# RT_SUPER__MK76__A.net
KiCad netlist of a schematic drawn in Altium Designer
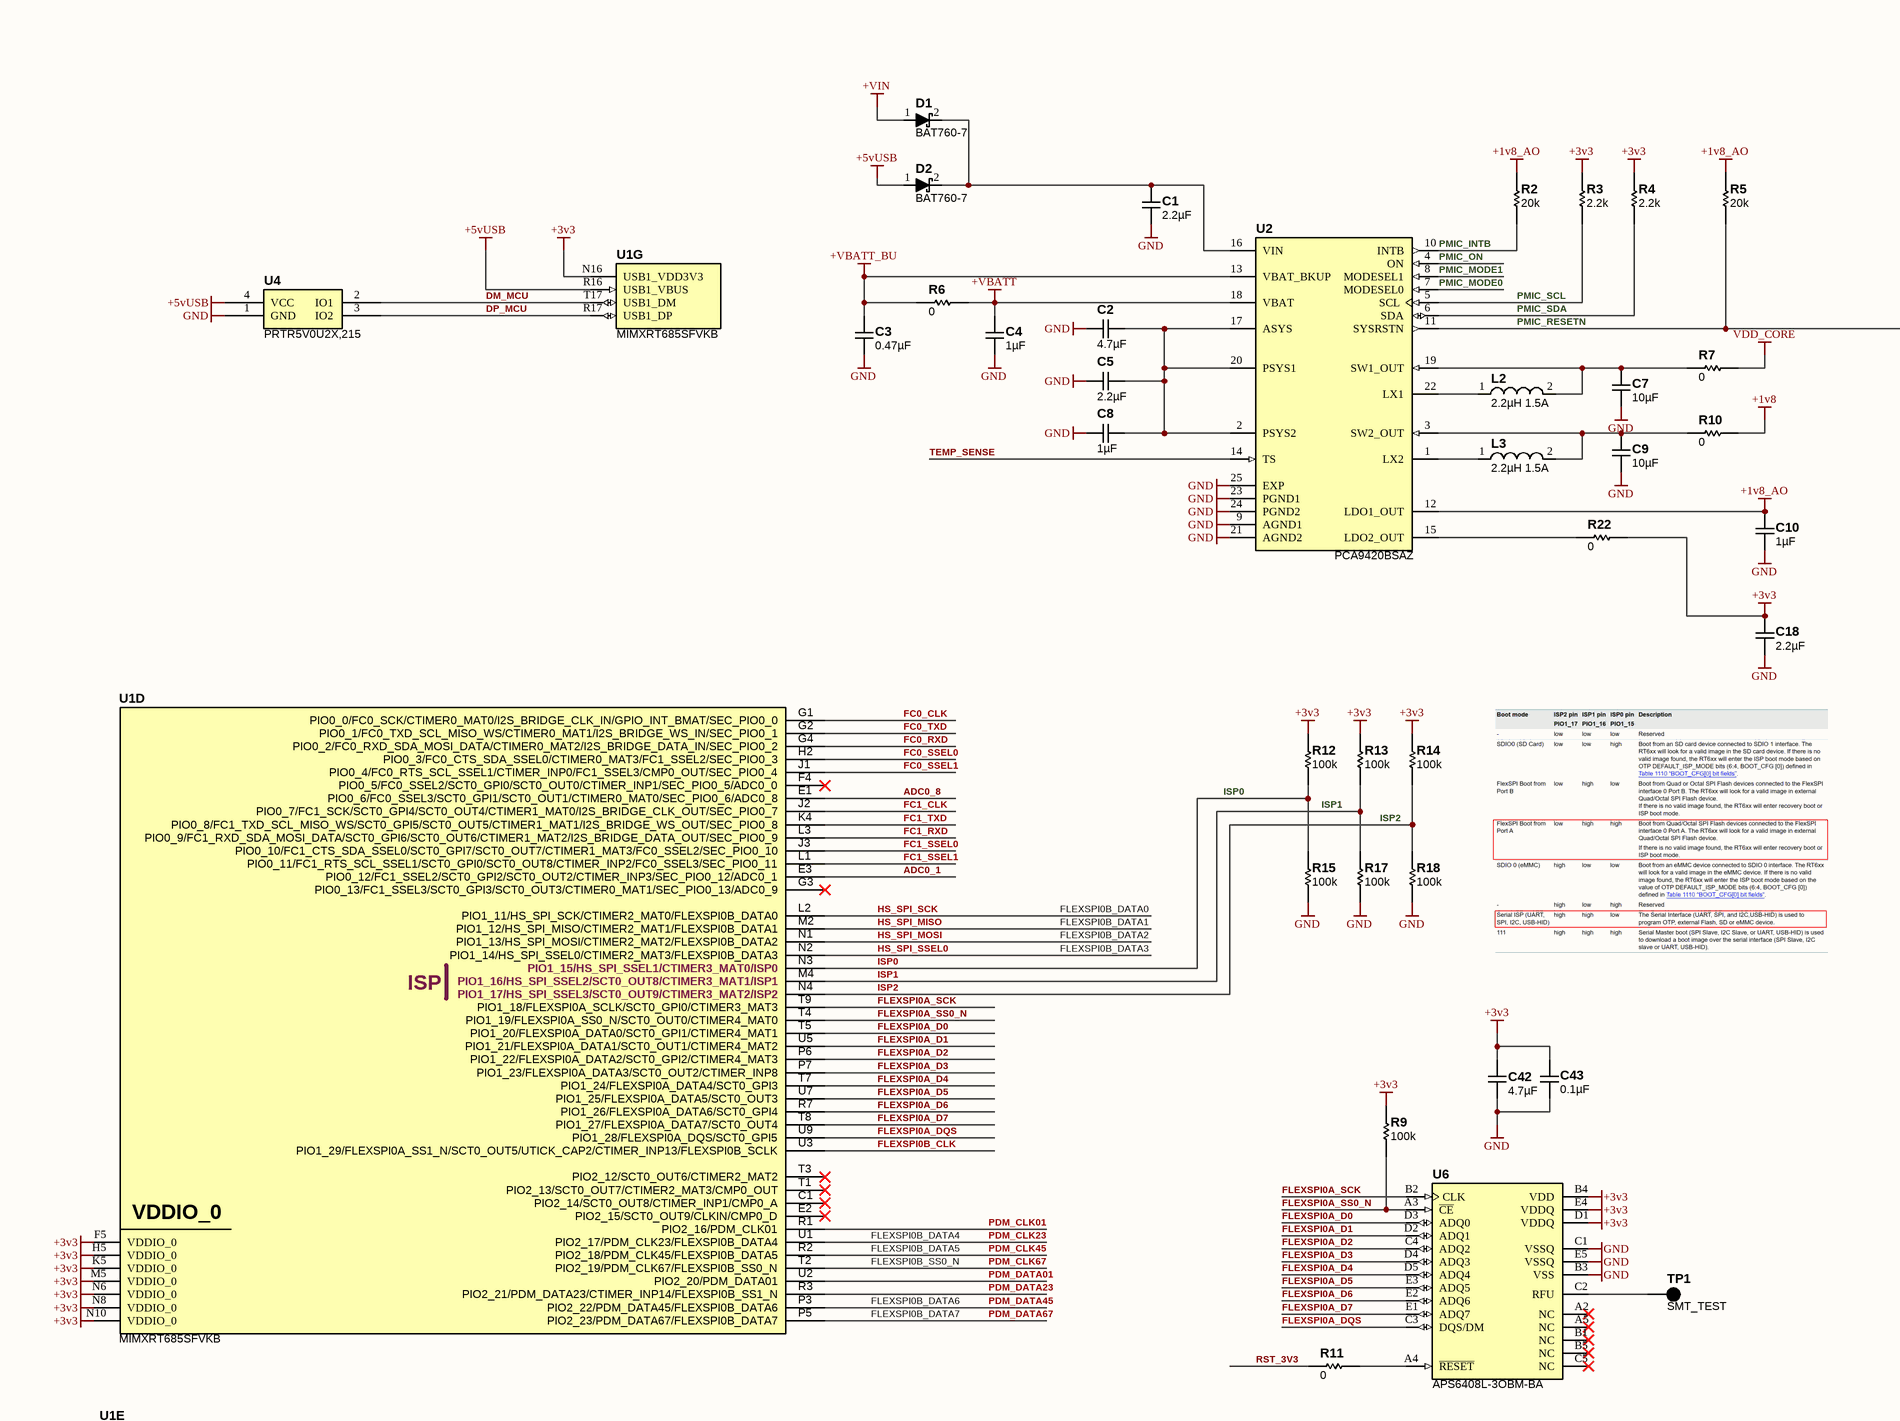
[diagram p0: RT_SUPER__MK76__A.SchDoc, top left]
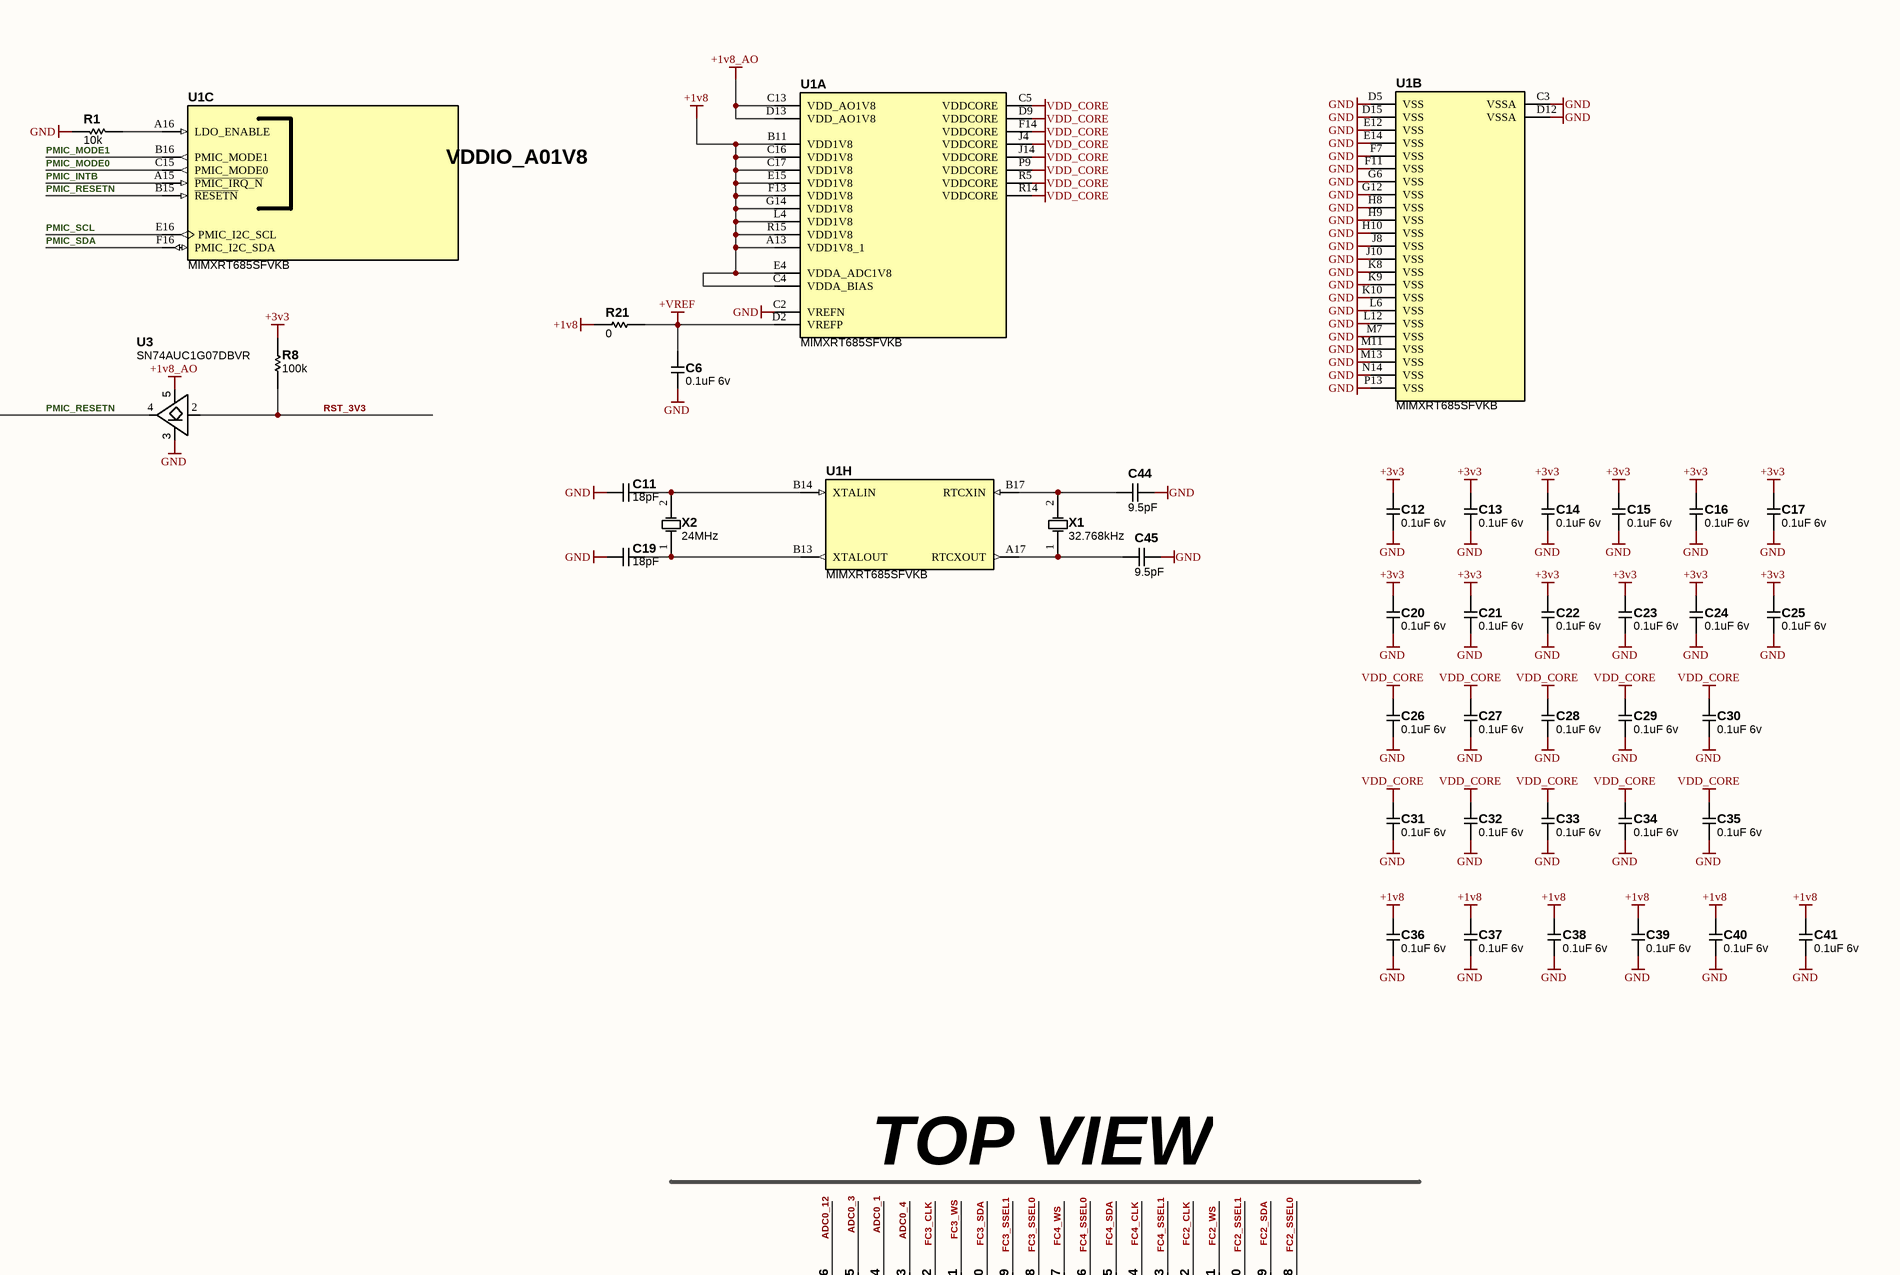
[diagram p1: RT_SUPER__MK76__A.SchDoc, top right]
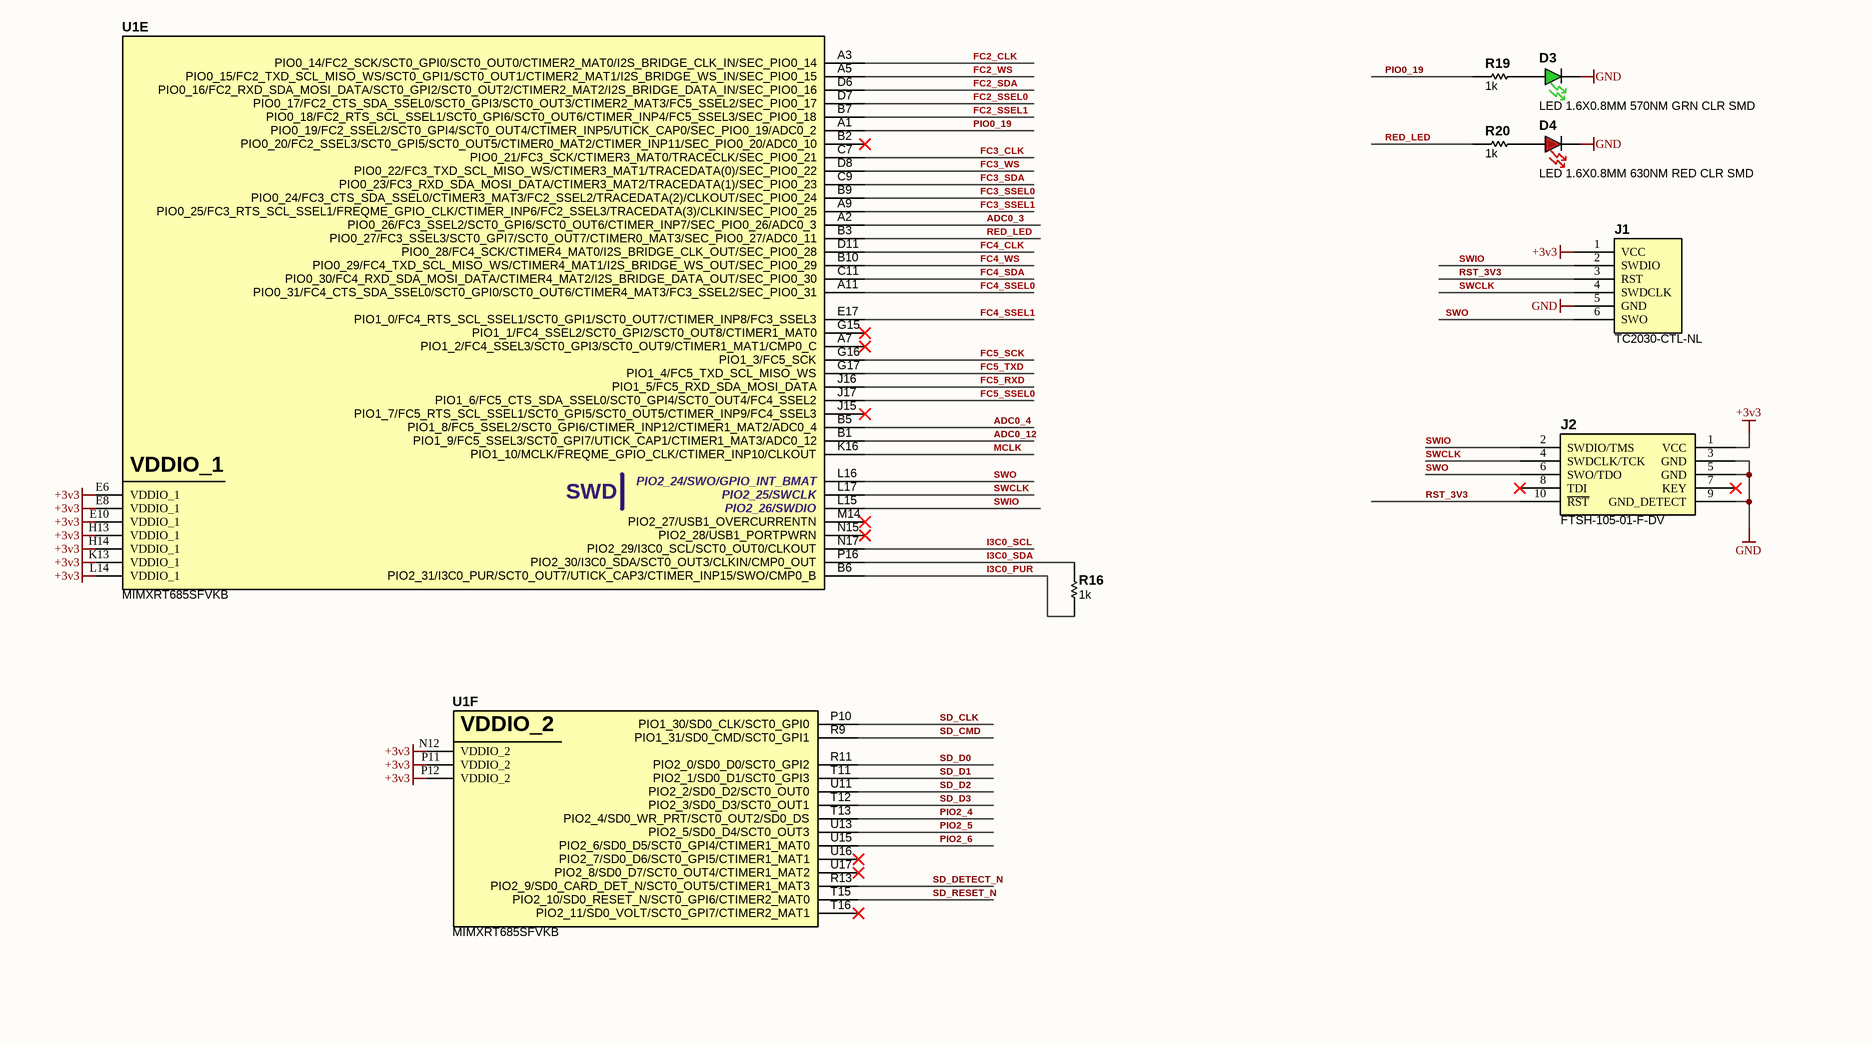
[diagram p2: RT_SUPER__MK76__A.SchDoc, bottom left]
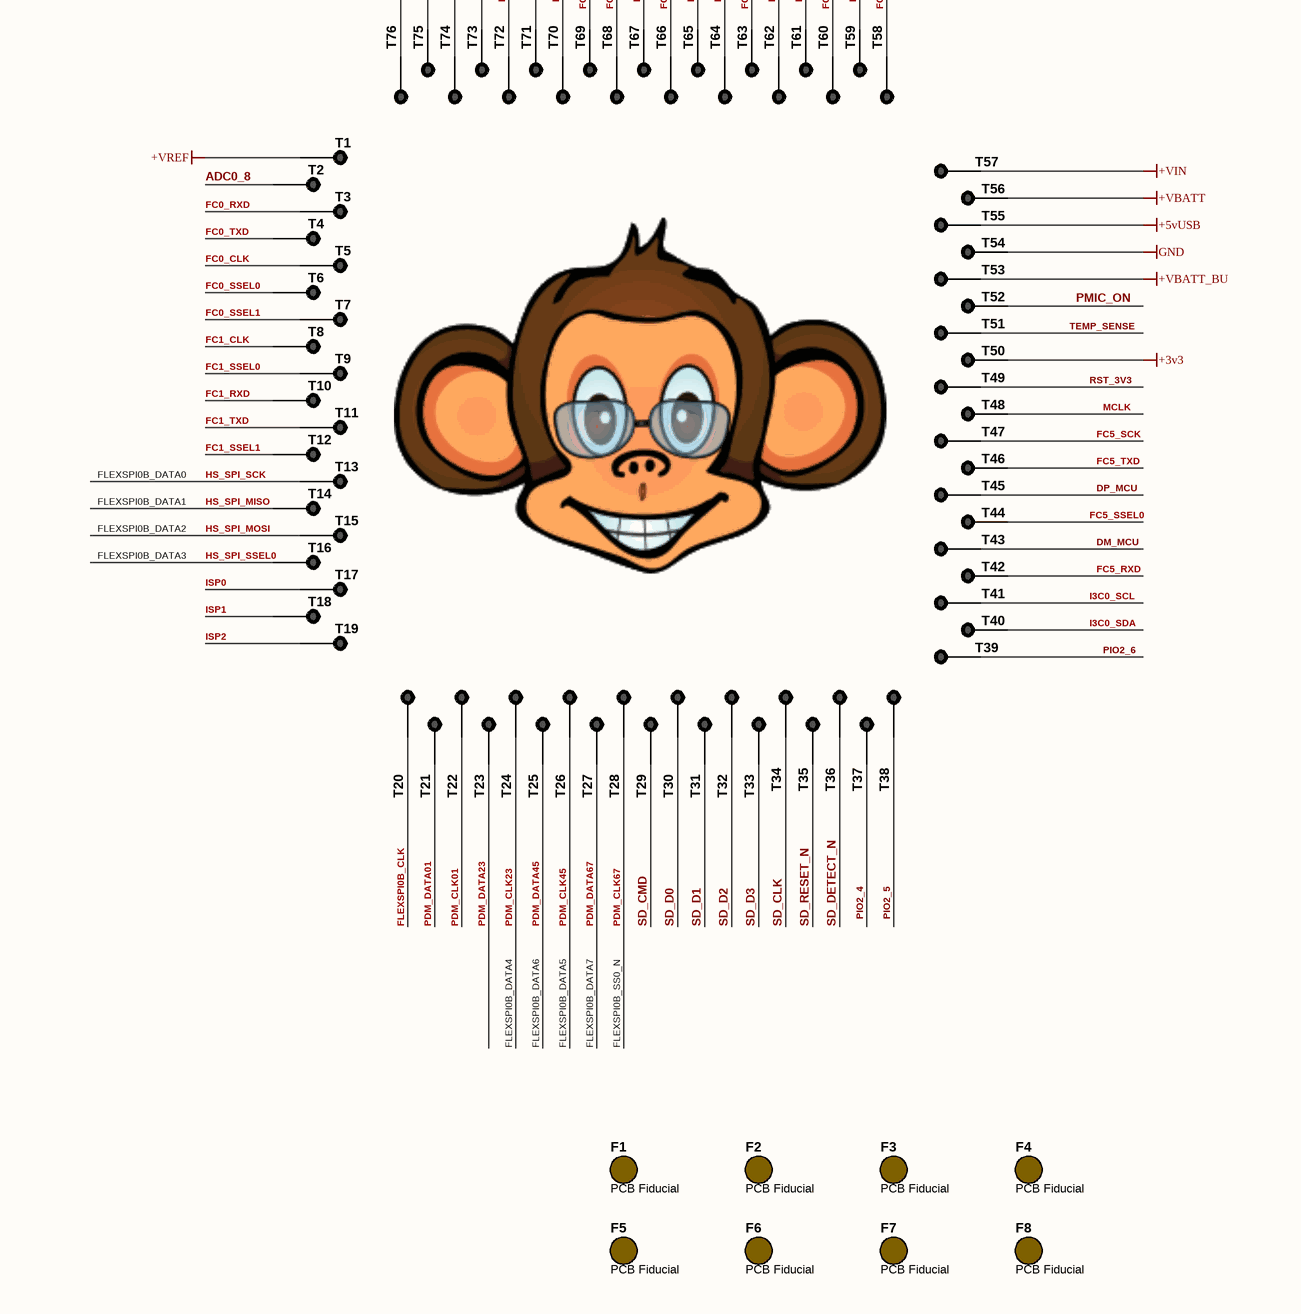
[diagram p3: RT_SUPER__MK76__A.SchDoc, bottom right]

(export (version "E")
  (design (tool "Eeschema 10.0.6"))
  (components
    (comp (ref "C1")
      (value "2.2µF")
      (footprint "C0603_0.90MM_MD")
      (description "CAP CER 2.2UF 6.3V X7R 0603")
      (fields
        (field (name "MANUFACTURER PART NUMBER") "GCM188R70J225KE22D")
        (field (name "MANUFACTURER") "Murata Electronics")
      )
      (libsource (lib "Capacitors - Murata - AEC-Q200") (part "C_2P_NP"))
    )
    (comp (ref "C2")
      (value "4.7µF")
      (footprint "C0603_1.00MM_MD")
      (description "CAP CER 4.7UF 6.3V X7S 0603")
      (fields
        (field (name "MANUFACTURER PART NUMBER") "GCJ188C70J475KE02D")
        (field (name "MANUFACTURER") "Murata Electronics")
      )
      (libsource (lib "Capacitors - Murata - AEC-Q200") (part "C_2P_NP"))
    )
    (comp (ref "C3")
      (value "0.47µF")
      (footprint "C0402_0.55MM_HD")
      (description "CAP CER 0.47UF 25V X5R 0402")
      (fields
        (field (name "MANUFACTURER PART NUMBER") "GRT155R61E474KE01D")
        (field (name "MANUFACTURER") "Murata Electronics")
      )
      (libsource (lib "Capacitors - Murata - AEC-Q200") (part "C_2P_NP"))
    )
    (comp (ref "C4")
      (value "1µF")
      (footprint "C0402_0.55MM_HD")
      (description "CAP CER 1UF 10V X7S 0402")
      (fields
        (field (name "MANUFACTURER PART NUMBER") "GCM155C71A105KE38D")
        (field (name "MANUFACTURER") "Murata Electronics")
      )
      (libsource (lib "Capacitors - Murata - AEC-Q200") (part "C_2P_NP"))
    )
    (comp (ref "C5")
      (value "2.2µF")
      (footprint "C0603_0.90MM_MD")
      (description "CAP CER 2.2UF 6.3V X7R 0603")
      (fields
        (field (name "MANUFACTURER PART NUMBER") "GCM188R70J225KE22D")
        (field (name "MANUFACTURER") "Murata Electronics")
      )
      (libsource (lib "Capacitors - Murata - AEC-Q200") (part "C_2P_NP"))
    )
    (comp (ref "C6")
      (value "0.1uF 6v")
      (footprint "C0201_PERFECT")
      (description "Cap Ceramic 0.1uF 6.3VDC X5R 10% SMD 0201 Paper T/R")
      (fields
        (field (name "MANUFACTURER PART NUMBER") "CC0201KRX5R5BB104")
        (field (name "MANUFACTURER") "Yageo")
      )
      (libsource (lib "eCapacitors") (part "CC0201KRX5R5BB104"))
    )
    (comp (ref "C7")
      (value "10µF")
      (footprint "C0603_0.90MM_MD")
      (description "CAP CER 10UF 10V X5R 0603")
      (fields
        (field (name "MANUFACTURER PART NUMBER") "GRT188R61A106ME13D")
        (field (name "MANUFACTURER") "Murata Electronics")
      )
      (libsource (lib "Capacitors - Murata - AEC-Q200") (part "C_2P_NP"))
    )
    (comp (ref "C8")
      (value "1µF")
      (footprint "C0402_0.55MM_HD")
      (description "CAP CER 1UF 10V X7S 0402")
      (fields
        (field (name "MANUFACTURER PART NUMBER") "GCM155C71A105KE38D")
        (field (name "MANUFACTURER") "Murata Electronics")
      )
      (libsource (lib "Capacitors - Murata - AEC-Q200") (part "C_2P_NP"))
    )
    (comp (ref "C9")
      (value "10µF")
      (footprint "C0603_0.90MM_MD")
      (description "CAP CER 10UF 10V X5R 0603")
      (fields
        (field (name "MANUFACTURER PART NUMBER") "GRT188R61A106ME13D")
        (field (name "MANUFACTURER") "Murata Electronics")
      )
      (libsource (lib "Capacitors - Murata - AEC-Q200") (part "C_2P_NP"))
    )
    (comp (ref "C10")
      (value "1µF")
      (footprint "C0402_0.55MM_HD")
      (description "CAP CER 1UF 10V X7S 0402")
      (fields
        (field (name "MANUFACTURER PART NUMBER") "GCM155C71A105KE38D")
        (field (name "MANUFACTURER") "Murata Electronics")
      )
      (libsource (lib "Capacitors - Murata - AEC-Q200") (part "C_2P_NP"))
    )
    (comp (ref "C11")
      (value "18pF")
      (footprint "C0402_0.55MM_HD")
      (description "CAP CER 18PF 50V C0G 0402")
      (fields
        (field (name "MANUFACTURER PART NUMBER") "CGA2B2C0G1H180J050BA")
        (field (name "MANUFACTURER") "TDK Corporation")
      )
      (libsource (lib "Capacitors - TDK- AEC-Q200") (part "C_2P_NP"))
    )
    (comp (ref "C12")
      (value "0.1uF 6v")
      (footprint "C0201_PERFECT")
      (description "Cap Ceramic 0.1uF 6.3VDC X5R 10% SMD 0201 Paper T/R")
      (fields
        (field (name "MANUFACTURER PART NUMBER") "CC0201KRX5R5BB104")
        (field (name "MANUFACTURER") "Yageo")
      )
      (libsource (lib "eCapacitors") (part "CC0201KRX5R5BB104"))
    )
    (comp (ref "C13")
      (value "0.1uF 6v")
      (footprint "C0201_PERFECT")
      (description "Cap Ceramic 0.1uF 6.3VDC X5R 10% SMD 0201 Paper T/R")
      (fields
        (field (name "MANUFACTURER PART NUMBER") "CC0201KRX5R5BB104")
        (field (name "MANUFACTURER") "Yageo")
      )
      (libsource (lib "eCapacitors") (part "CC0201KRX5R5BB104"))
    )
    (comp (ref "C14")
      (value "0.1uF 6v")
      (footprint "C0201_PERFECT")
      (description "Cap Ceramic 0.1uF 6.3VDC X5R 10% SMD 0201 Paper T/R")
      (fields
        (field (name "MANUFACTURER PART NUMBER") "CC0201KRX5R5BB104")
        (field (name "MANUFACTURER") "Yageo")
      )
      (libsource (lib "eCapacitors") (part "CC0201KRX5R5BB104"))
    )
    (comp (ref "C15")
      (value "0.1uF 6v")
      (footprint "C0201_PERFECT")
      (description "Cap Ceramic 0.1uF 6.3VDC X5R 10% SMD 0201 Paper T/R")
      (fields
        (field (name "MANUFACTURER PART NUMBER") "CC0201KRX5R5BB104")
        (field (name "MANUFACTURER") "Yageo")
      )
      (libsource (lib "eCapacitors") (part "CC0201KRX5R5BB104"))
    )
    (comp (ref "C16")
      (value "0.1uF 6v")
      (footprint "C0201_PERFECT")
      (description "Cap Ceramic 0.1uF 6.3VDC X5R 10% SMD 0201 Paper T/R")
      (fields
        (field (name "MANUFACTURER PART NUMBER") "CC0201KRX5R5BB104")
        (field (name "MANUFACTURER") "Yageo")
      )
      (libsource (lib "eCapacitors") (part "CC0201KRX5R5BB104"))
    )
    (comp (ref "C17")
      (value "0.1uF 6v")
      (footprint "C0201_PERFECT")
      (description "Cap Ceramic 0.1uF 6.3VDC X5R 10% SMD 0201 Paper T/R")
      (fields
        (field (name "MANUFACTURER PART NUMBER") "CC0201KRX5R5BB104")
        (field (name "MANUFACTURER") "Yageo")
      )
      (libsource (lib "eCapacitors") (part "CC0201KRX5R5BB104"))
    )
    (comp (ref "C18")
      (value "2.2µF")
      (footprint "C0603_0.90MM_MD")
      (description "CAP CER 2.2UF 6.3V X7R 0603")
      (fields
        (field (name "MANUFACTURER PART NUMBER") "GCM188R70J225KE22D")
        (field (name "MANUFACTURER") "Murata Electronics")
      )
      (libsource (lib "Capacitors - Murata - AEC-Q200") (part "C_2P_NP"))
    )
    (comp (ref "C19")
      (value "18pF")
      (footprint "C0402_0.55MM_HD")
      (description "CAP CER 18PF 50V C0G 0402")
      (fields
        (field (name "MANUFACTURER PART NUMBER") "CGA2B2C0G1H180J050BA")
        (field (name "MANUFACTURER") "TDK Corporation")
      )
      (libsource (lib "Capacitors - TDK- AEC-Q200") (part "C_2P_NP"))
    )
    (comp (ref "C20")
      (value "0.1uF 6v")
      (footprint "C0201_PERFECT")
      (description "Cap Ceramic 0.1uF 6.3VDC X5R 10% SMD 0201 Paper T/R")
      (fields
        (field (name "MANUFACTURER PART NUMBER") "CC0201KRX5R5BB104")
        (field (name "MANUFACTURER") "Yageo")
      )
      (libsource (lib "eCapacitors") (part "CC0201KRX5R5BB104"))
    )
    (comp (ref "C21")
      (value "0.1uF 6v")
      (footprint "C0201_PERFECT")
      (description "Cap Ceramic 0.1uF 6.3VDC X5R 10% SMD 0201 Paper T/R")
      (fields
        (field (name "MANUFACTURER PART NUMBER") "CC0201KRX5R5BB104")
        (field (name "MANUFACTURER") "Yageo")
      )
      (libsource (lib "eCapacitors") (part "CC0201KRX5R5BB104"))
    )
    (comp (ref "C22")
      (value "0.1uF 6v")
      (footprint "C0201_PERFECT")
      (description "Cap Ceramic 0.1uF 6.3VDC X5R 10% SMD 0201 Paper T/R")
      (fields
        (field (name "MANUFACTURER PART NUMBER") "CC0201KRX5R5BB104")
        (field (name "MANUFACTURER") "Yageo")
      )
      (libsource (lib "eCapacitors") (part "CC0201KRX5R5BB104"))
    )
    (comp (ref "C23")
      (value "0.1uF 6v")
      (footprint "C0201_PERFECT")
      (description "Cap Ceramic 0.1uF 6.3VDC X5R 10% SMD 0201 Paper T/R")
      (fields
        (field (name "MANUFACTURER PART NUMBER") "CC0201KRX5R5BB104")
        (field (name "MANUFACTURER") "Yageo")
      )
      (libsource (lib "eCapacitors") (part "CC0201KRX5R5BB104"))
    )
    (comp (ref "C24")
      (value "0.1uF 6v")
      (footprint "C0201_PERFECT")
      (description "Cap Ceramic 0.1uF 6.3VDC X5R 10% SMD 0201 Paper T/R")
      (fields
        (field (name "MANUFACTURER PART NUMBER") "CC0201KRX5R5BB104")
        (field (name "MANUFACTURER") "Yageo")
      )
      (libsource (lib "eCapacitors") (part "CC0201KRX5R5BB104"))
    )
    (comp (ref "C25")
      (value "0.1uF 6v")
      (footprint "C0201_PERFECT")
      (description "Cap Ceramic 0.1uF 6.3VDC X5R 10% SMD 0201 Paper T/R")
      (fields
        (field (name "MANUFACTURER PART NUMBER") "CC0201KRX5R5BB104")
        (field (name "MANUFACTURER") "Yageo")
      )
      (libsource (lib "eCapacitors") (part "CC0201KRX5R5BB104"))
    )
    (comp (ref "C26")
      (value "0.1uF 6v")
      (footprint "C0201_PERFECT")
      (description "Cap Ceramic 0.1uF 6.3VDC X5R 10% SMD 0201 Paper T/R")
      (fields
        (field (name "MANUFACTURER PART NUMBER") "CC0201KRX5R5BB104")
        (field (name "MANUFACTURER") "Yageo")
      )
      (libsource (lib "eCapacitors") (part "CC0201KRX5R5BB104"))
    )
    (comp (ref "C27")
      (value "0.1uF 6v")
      (footprint "C0201_PERFECT")
      (description "Cap Ceramic 0.1uF 6.3VDC X5R 10% SMD 0201 Paper T/R")
      (fields
        (field (name "MANUFACTURER PART NUMBER") "CC0201KRX5R5BB104")
        (field (name "MANUFACTURER") "Yageo")
      )
      (libsource (lib "eCapacitors") (part "CC0201KRX5R5BB104"))
    )
    (comp (ref "C28")
      (value "0.1uF 6v")
      (footprint "C0201_PERFECT")
      (description "Cap Ceramic 0.1uF 6.3VDC X5R 10% SMD 0201 Paper T/R")
      (fields
        (field (name "MANUFACTURER PART NUMBER") "CC0201KRX5R5BB104")
        (field (name "MANUFACTURER") "Yageo")
      )
      (libsource (lib "eCapacitors") (part "CC0201KRX5R5BB104"))
    )
    (comp (ref "C29")
      (value "0.1uF 6v")
      (footprint "C0201_PERFECT")
      (description "Cap Ceramic 0.1uF 6.3VDC X5R 10% SMD 0201 Paper T/R")
      (fields
        (field (name "MANUFACTURER PART NUMBER") "CC0201KRX5R5BB104")
        (field (name "MANUFACTURER") "Yageo")
      )
      (libsource (lib "eCapacitors") (part "CC0201KRX5R5BB104"))
    )
    (comp (ref "C30")
      (value "0.1uF 6v")
      (footprint "C0201_PERFECT")
      (description "Cap Ceramic 0.1uF 6.3VDC X5R 10% SMD 0201 Paper T/R")
      (fields
        (field (name "MANUFACTURER PART NUMBER") "CC0201KRX5R5BB104")
        (field (name "MANUFACTURER") "Yageo")
      )
      (libsource (lib "eCapacitors") (part "CC0201KRX5R5BB104"))
    )
    (comp (ref "C31")
      (value "0.1uF 6v")
      (footprint "C0201_PERFECT")
      (description "Cap Ceramic 0.1uF 6.3VDC X5R 10% SMD 0201 Paper T/R")
      (fields
        (field (name "MANUFACTURER PART NUMBER") "CC0201KRX5R5BB104")
        (field (name "MANUFACTURER") "Yageo")
      )
      (libsource (lib "eCapacitors") (part "CC0201KRX5R5BB104"))
    )
    (comp (ref "C32")
      (value "0.1uF 6v")
      (footprint "C0201_PERFECT")
      (description "Cap Ceramic 0.1uF 6.3VDC X5R 10% SMD 0201 Paper T/R")
      (fields
        (field (name "MANUFACTURER PART NUMBER") "CC0201KRX5R5BB104")
        (field (name "MANUFACTURER") "Yageo")
      )
      (libsource (lib "eCapacitors") (part "CC0201KRX5R5BB104"))
    )
    (comp (ref "C33")
      (value "0.1uF 6v")
      (footprint "C0201_PERFECT")
      (description "Cap Ceramic 0.1uF 6.3VDC X5R 10% SMD 0201 Paper T/R")
      (fields
        (field (name "MANUFACTURER PART NUMBER") "CC0201KRX5R5BB104")
        (field (name "MANUFACTURER") "Yageo")
      )
      (libsource (lib "eCapacitors") (part "CC0201KRX5R5BB104"))
    )
    (comp (ref "C34")
      (value "0.1uF 6v")
      (footprint "C0201_PERFECT")
      (description "Cap Ceramic 0.1uF 6.3VDC X5R 10% SMD 0201 Paper T/R")
      (fields
        (field (name "MANUFACTURER PART NUMBER") "CC0201KRX5R5BB104")
        (field (name "MANUFACTURER") "Yageo")
      )
      (libsource (lib "eCapacitors") (part "CC0201KRX5R5BB104"))
    )
    (comp (ref "C35")
      (value "0.1uF 6v")
      (footprint "C0201_PERFECT")
      (description "Cap Ceramic 0.1uF 6.3VDC X5R 10% SMD 0201 Paper T/R")
      (fields
        (field (name "MANUFACTURER PART NUMBER") "CC0201KRX5R5BB104")
        (field (name "MANUFACTURER") "Yageo")
      )
      (libsource (lib "eCapacitors") (part "CC0201KRX5R5BB104"))
    )
    (comp (ref "C36")
      (value "0.1uF 6v")
      (footprint "C0201_PERFECT")
      (description "Cap Ceramic 0.1uF 6.3VDC X5R 10% SMD 0201 Paper T/R")
      (fields
        (field (name "MANUFACTURER PART NUMBER") "CC0201KRX5R5BB104")
        (field (name "MANUFACTURER") "Yageo")
      )
      (libsource (lib "eCapacitors") (part "CC0201KRX5R5BB104"))
    )
    (comp (ref "C37")
      (value "0.1uF 6v")
      (footprint "C0201_PERFECT")
      (description "Cap Ceramic 0.1uF 6.3VDC X5R 10% SMD 0201 Paper T/R")
      (fields
        (field (name "MANUFACTURER PART NUMBER") "CC0201KRX5R5BB104")
        (field (name "MANUFACTURER") "Yageo")
      )
      (libsource (lib "eCapacitors") (part "CC0201KRX5R5BB104"))
    )
    (comp (ref "C38")
      (value "0.1uF 6v")
      (footprint "C0201_PERFECT")
      (description "Cap Ceramic 0.1uF 6.3VDC X5R 10% SMD 0201 Paper T/R")
      (fields
        (field (name "MANUFACTURER PART NUMBER") "CC0201KRX5R5BB104")
        (field (name "MANUFACTURER") "Yageo")
      )
      (libsource (lib "eCapacitors") (part "CC0201KRX5R5BB104"))
    )
    (comp (ref "C39")
      (value "0.1uF 6v")
      (footprint "C0201_PERFECT")
      (description "Cap Ceramic 0.1uF 6.3VDC X5R 10% SMD 0201 Paper T/R")
      (fields
        (field (name "MANUFACTURER PART NUMBER") "CC0201KRX5R5BB104")
        (field (name "MANUFACTURER") "Yageo")
      )
      (libsource (lib "eCapacitors") (part "CC0201KRX5R5BB104"))
    )
    (comp (ref "C40")
      (value "0.1uF 6v")
      (footprint "C0201_PERFECT")
      (description "Cap Ceramic 0.1uF 6.3VDC X5R 10% SMD 0201 Paper T/R")
      (fields
        (field (name "MANUFACTURER PART NUMBER") "CC0201KRX5R5BB104")
        (field (name "MANUFACTURER") "Yageo")
      )
      (libsource (lib "eCapacitors") (part "CC0201KRX5R5BB104"))
    )
    (comp (ref "C41")
      (value "0.1uF 6v")
      (footprint "C0201_PERFECT")
      (description "Cap Ceramic 0.1uF 6.3VDC X5R 10% SMD 0201 Paper T/R")
      (fields
        (field (name "MANUFACTURER PART NUMBER") "CC0201KRX5R5BB104")
        (field (name "MANUFACTURER") "Yageo")
      )
      (libsource (lib "eCapacitors") (part "CC0201KRX5R5BB104"))
    )
    (comp (ref "C42")
      (value "4.7µF")
      (footprint "C0603_1.00MM_MD")
      (description "CAP CER 4.7UF 6.3V X7S 0603")
      (fields
        (field (name "MANUFACTURER PART NUMBER") "GCJ188C70J475KE02D")
        (field (name "MANUFACTURER") "Murata Electronics")
      )
      (libsource (lib "Capacitors - Murata - AEC-Q200") (part "C_2P_NP"))
    )
    (comp (ref "C43")
      (value "0.1µF")
      (footprint "C0402_0.55MM_MD")
      (description "CAP CER 0.1UF 16V X7R 0402")
      (fields
        (field (name "MANUFACTURER PART NUMBER") "CGA2B1X7R1C104K050BC")
        (field (name "MANUFACTURER") "TDK Corporation")
      )
      (libsource (lib "Capacitors - TDK- AEC-Q200") (part "C_2P_NP"))
    )
    (comp (ref "C44")
      (value "9.5pF")
      (footprint "PERFECT_0402")
      (description "CAP CER 9.5PF 50V C0G/NP0 0402")
      (fields
        (field (name "MANUFACTURER PART NUMBER") "GCQ1555C1H9R5BB01D")
        (field (name "MANUFACTURER") "Murata Electronics")
      )
      (libsource (lib "Capacitors - Murata - AEC-Q200") (part "C_2P_NP"))
    )
    (comp (ref "C45")
      (value "9.5pF")
      (footprint "PERFECT_0402")
      (description "CAP CER 9.5PF 50V C0G/NP0 0402")
      (fields
        (field (name "MANUFACTURER PART NUMBER") "GCQ1555C1H9R5BB01D")
        (field (name "MANUFACTURER") "Murata Electronics")
      )
      (libsource (lib "Capacitors - Murata - AEC-Q200") (part "C_2P_NP"))
    )
    (comp (ref "D1")
      (value "BAT760-7")
      (footprint "D_SOD-323_P")
      (description "DIODE SCHOTTKY 30V 1A SOD323")
      (fields (field (name "MANUFACTURER") "Diodes Inc"))
      (libsource (lib "Diodes") (part "DS_1A_2C"))
    )
    (comp (ref "D2")
      (value "BAT760-7")
      (footprint "D_SOD-323_P")
      (description "DIODE SCHOTTKY 30V 1A SOD323")
      (fields (field (name "MANUFACTURER") "Diodes Inc"))
      (libsource (lib "Diodes") (part "DS_1A_2C"))
    )
    (comp (ref "D3")
      (value "LED 1.6X0.8MM 570NM GRN CLR SMD")
      (footprint "LED_0603 - GREEN")
      (fields
        (field (name "MANUFACTURER") "Kingbright Corp")
        (field (name "MANUFACTURER PART NUMBER") "APT1608CGCK")
      )
      (libsource (lib "eDiode") (part "APT1608CGCK"))
    )
    (comp (ref "D4")
      (value "LED 1.6X0.8MM 630NM RED CLR SMD")
      (footprint "LED_0603 - RED")
      (fields
        (field (name "MANUFACTURER") "Kingbright Corp")
        (field (name "MANUFACTURER PART NUMBER") "APT1608SURCK")
      )
      (libsource (lib "eDiode") (part "APT1608SURCK"))
    )
    (comp (ref "F1")
      (value "PCB Fiducial")
      (footprint "Fiducial 1mm - 2mm")
      (libsource (lib "eFiducial") (part "Fiducial"))
    )
    (comp (ref "F2")
      (value "PCB Fiducial")
      (footprint "Fiducial 1mm - 2mm")
      (libsource (lib "eFiducial") (part "Fiducial"))
    )
    (comp (ref "F3")
      (value "PCB Fiducial")
      (footprint "Fiducial 1mm - 2mm")
      (libsource (lib "eFiducial") (part "Fiducial"))
    )
    (comp (ref "F4")
      (value "PCB Fiducial")
      (footprint "Fiducial 1mm - 2mm")
      (libsource (lib "eFiducial") (part "Fiducial"))
    )
    (comp (ref "F5")
      (value "PCB Fiducial")
      (footprint "Fiducial 1mm - 2mm")
      (libsource (lib "eFiducial") (part "Fiducial"))
    )
    (comp (ref "F6")
      (value "PCB Fiducial")
      (footprint "Fiducial 1mm - 2mm")
      (libsource (lib "eFiducial") (part "Fiducial"))
    )
    (comp (ref "F7")
      (value "PCB Fiducial")
      (footprint "Fiducial 1mm - 2mm")
      (libsource (lib "eFiducial") (part "Fiducial"))
    )
    (comp (ref "F8")
      (value "PCB Fiducial")
      (footprint "Fiducial 1mm - 2mm")
      (libsource (lib "eFiducial") (part "Fiducial"))
    )
    (comp (ref "J1")
      (value "TC2030‐CTL‐NL")
      (footprint "TC2030 NO LATCH")
      (description "Tag Connect Pads - No latching Clips - ARM")
      (libsource (lib "eConnector_Debug") (part "TC2030‐CTL‐NL"))
    )
    (comp (ref "J2")
      (value "FTSH-105-01-F-DV")
      (footprint "FTSH-105-01-F-DV-K-A")
      (description "SAMTEC - FTSH-105-01-F-DV - .050 X .050")
      (fields (field (name "MANUFACTURER") "SAMTEC"))
      (libsource (lib "eConnector") (part "CORTEX-DEBUG"))
    )
    (comp (ref "L2")
      (value "2.2µH 1.5A")
      (footprint "L_NRH3012")
      (description "Inductor 2.2µH 1.5A")
      (fields
        (field (name "MANUFACTURER PART NUMBER") "NRH3012T2R2MN")
        (field (name "MANUFACTURER") "Taiyo Yuden")
      )
      (libsource (lib "Inductors") (part "L_2P"))
    )
    (comp (ref "L3")
      (value "2.2µH 1.5A")
      (footprint "L_NRH3012")
      (description "Inductor 2.2µH 1.5A")
      (fields
        (field (name "MANUFACTURER PART NUMBER") "NRH3012T2R2MN")
        (field (name "MANUFACTURER") "Taiyo Yuden")
      )
      (libsource (lib "Inductors") (part "L_2P"))
    )
    (comp (ref "R1")
      (value "10k")
      (footprint "R0402_0.40MM_HD")
      (description "RES 10K OHM 1/10W 1% 0402 SMD")
      (fields
        (field (name "MANUFACTURER PART NUMBER") "ERJ-2RKF1002X")
        (field (name "MANUFACTURER") "Panasonic Electronic Components")
      )
      (libsource (lib "Resistors - Panasonic - AEC-Q200") (part "R_2P"))
    )
    (comp (ref "R2")
      (value "20k")
      (footprint "R0402_0.40MM_HD")
      (description "RES 20K OHM 1/10W 1% 0402 SMD")
      (fields
        (field (name "MANUFACTURER PART NUMBER") "ERJ-2RKF2002X")
        (field (name "MANUFACTURER") "Panasonic Electronic Components")
      )
      (libsource (lib "Resistors - Panasonic - AEC-Q200") (part "R_2P"))
    )
    (comp (ref "R3")
      (value "2.2k")
      (footprint "R0402_0.40MM_HD")
      (description "RES 2.2K OHM 1/10W 1% 0402 SMD")
      (fields
        (field (name "MANUFACTURER PART NUMBER") "ERJ-2RKF2201X")
        (field (name "MANUFACTURER") "Panasonic Electronic Components")
      )
      (libsource (lib "Resistors - Panasonic - AEC-Q200") (part "R_2P"))
    )
    (comp (ref "R4")
      (value "2.2k")
      (footprint "R0402_0.40MM_HD")
      (description "RES 2.2K OHM 1/10W 1% 0402 SMD")
      (fields
        (field (name "MANUFACTURER PART NUMBER") "ERJ-2RKF2201X")
        (field (name "MANUFACTURER") "Panasonic Electronic Components")
      )
      (libsource (lib "Resistors - Panasonic - AEC-Q200") (part "R_2P"))
    )
    (comp (ref "R5")
      (value "20k")
      (footprint "R0402_0.40MM_HD")
      (description "RES 20K OHM 1/10W 1% 0402 SMD")
      (fields
        (field (name "MANUFACTURER PART NUMBER") "ERJ-2RKF2002X")
        (field (name "MANUFACTURER") "Panasonic Electronic Components")
      )
      (libsource (lib "Resistors - Panasonic - AEC-Q200") (part "R_2P"))
    )
    (comp (ref "R6")
      (value "0")
      (footprint "R0402_0.40MM_HD")
      (description "RES 0.0 OHM 1/10W JUMP 0402 SMD")
      (fields
        (field (name "MANUFACTURER PART NUMBER") "ERJ-2GE0R00X")
        (field (name "MANUFACTURER") "Panasonic Electronic Components")
      )
      (libsource (lib "Resistors - Panasonic - AEC-Q200") (part "R_2P"))
    )
    (comp (ref "R7")
      (value "0")
      (footprint "R0402_0.40MM_HD")
      (description "RES 0.0 OHM 1/10W JUMP 0402 SMD")
      (fields
        (field (name "MANUFACTURER PART NUMBER") "ERJ-2GE0R00X")
        (field (name "MANUFACTURER") "Panasonic Electronic Components")
      )
      (libsource (lib "Resistors - Panasonic - AEC-Q200") (part "R_2P"))
    )
    (comp (ref "R8")
      (value "100k")
      (footprint "R0402_0.40MM_HD")
      (description "RES 100K OHM 1/10W 1% 0402 SMD")
      (fields
        (field (name "MANUFACTURER PART NUMBER") "ERJ-2RKF1003X")
        (field (name "MANUFACTURER") "Panasonic Electronic Components")
      )
      (libsource (lib "Resistors - Panasonic - AEC-Q200") (part "R_2P"))
    )
    (comp (ref "R9")
      (value "100k")
      (footprint "R0402_0.40MM_HD")
      (description "RES 100K OHM 1/10W 1% 0402 SMD")
      (fields
        (field (name "MANUFACTURER PART NUMBER") "ERJ-2RKF1003X")
        (field (name "MANUFACTURER") "Panasonic Electronic Components")
      )
      (libsource (lib "Resistors - Panasonic - AEC-Q200") (part "R_2P"))
    )
    (comp (ref "R10")
      (value "0")
      (footprint "R0402_0.40MM_HD")
      (description "RES 0.0 OHM 1/10W JUMP 0402 SMD")
      (fields
        (field (name "MANUFACTURER PART NUMBER") "ERJ-2GE0R00X")
        (field (name "MANUFACTURER") "Panasonic Electronic Components")
      )
      (libsource (lib "Resistors - Panasonic - AEC-Q200") (part "R_2P"))
    )
    (comp (ref "R11")
      (value "0")
      (footprint "R0402_0.40MM_HD")
      (description "RES 0.0 OHM 1/10W JUMP 0402 SMD")
      (fields
        (field (name "MANUFACTURER PART NUMBER") "ERJ-2GE0R00X")
        (field (name "MANUFACTURER") "Panasonic Electronic Components")
      )
      (libsource (lib "Resistors - Panasonic - AEC-Q200") (part "R_2P"))
    )
    (comp (ref "R12")
      (value "100k")
      (footprint "R0402_0.40MM_HD")
      (description "RES 100K OHM 1/10W 1% 0402 SMD")
      (fields
        (field (name "MANUFACTURER PART NUMBER") "ERJ-2RKF1003X")
        (field (name "MANUFACTURER") "Panasonic Electronic Components")
      )
      (libsource (lib "Resistors - Panasonic - AEC-Q200") (part "R_2P"))
    )
    (comp (ref "R13")
      (value "100k")
      (footprint "R0402_0.40MM_HD")
      (description "RES 100K OHM 1/10W 1% 0402 SMD")
      (fields
        (field (name "MANUFACTURER PART NUMBER") "ERJ-2RKF1003X")
        (field (name "MANUFACTURER") "Panasonic Electronic Components")
      )
      (libsource (lib "Resistors - Panasonic - AEC-Q200") (part "R_2P"))
    )
    (comp (ref "R14")
      (value "100k")
      (footprint "R0402_0.40MM_HD")
      (description "RES 100K OHM 1/10W 1% 0402 SMD")
      (fields
        (field (name "MANUFACTURER PART NUMBER") "ERJ-2RKF1003X")
        (field (name "MANUFACTURER") "Panasonic Electronic Components")
      )
      (libsource (lib "Resistors - Panasonic - AEC-Q200") (part "R_2P"))
    )
    (comp (ref "R15")
      (value "100k")
      (footprint "R0402_0.40MM_HD")
      (description "RES 100K OHM 1/10W 1% 0402 SMD")
      (fields
        (field (name "MANUFACTURER PART NUMBER") "ERJ-2RKF1003X")
        (field (name "MANUFACTURER") "Panasonic Electronic Components")
      )
      (libsource (lib "Resistors - Panasonic - AEC-Q200") (part "R_2P"))
    )
    (comp (ref "R16")
      (value "1k")
      (footprint "R0402_0.40MM_HD")
      (description "RES 1K OHM 1/10W 1% 0402 SMD")
      (fields
        (field (name "MANUFACTURER PART NUMBER") "ERJ-2RKF1001X")
        (field (name "MANUFACTURER") "Panasonic Electronic Components")
      )
      (libsource (lib "Resistors - Panasonic - AEC-Q200") (part "R_2P"))
    )
    (comp (ref "R17")
      (value "100k")
      (footprint "R0402_0.40MM_HD")
      (description "RES 100K OHM 1/10W 1% 0402 SMD")
      (fields
        (field (name "MANUFACTURER PART NUMBER") "ERJ-2RKF1003X")
        (field (name "MANUFACTURER") "Panasonic Electronic Components")
      )
      (libsource (lib "Resistors - Panasonic - AEC-Q200") (part "R_2P"))
    )
    (comp (ref "R18")
      (value "100k")
      (footprint "R0402_0.40MM_HD")
      (description "RES 100K OHM 1/10W 1% 0402 SMD")
      (fields
        (field (name "MANUFACTURER PART NUMBER") "ERJ-2RKF1003X")
        (field (name "MANUFACTURER") "Panasonic Electronic Components")
      )
      (libsource (lib "Resistors - Panasonic - AEC-Q200") (part "R_2P"))
    )
    (comp (ref "R19")
      (value "1k")
      (footprint "R0402_0.40MM_HD")
      (description "RES 1K OHM 1/10W 1% 0402 SMD")
      (fields
        (field (name "MANUFACTURER PART NUMBER") "ERJ-2RKF1001X")
        (field (name "MANUFACTURER") "Panasonic Electronic Components")
      )
      (libsource (lib "Resistors - Panasonic - AEC-Q200") (part "R_2P"))
    )
    (comp (ref "R20")
      (value "1k")
      (footprint "R0402_0.40MM_HD")
      (description "RES 1K OHM 1/10W 1% 0402 SMD")
      (fields
        (field (name "MANUFACTURER PART NUMBER") "ERJ-2RKF1001X")
        (field (name "MANUFACTURER") "Panasonic Electronic Components")
      )
      (libsource (lib "Resistors - Panasonic - AEC-Q200") (part "R_2P"))
    )
    (comp (ref "R21")
      (value "0")
      (footprint "R0402_0.40MM_HD")
      (description "RES 0.0 OHM 1/10W JUMP 0402 SMD")
      (fields
        (field (name "MANUFACTURER PART NUMBER") "ERJ-2GE0R00X")
        (field (name "MANUFACTURER") "Panasonic Electronic Components")
      )
      (libsource (lib "Resistors - Panasonic - AEC-Q200") (part "R_2P"))
    )
    (comp (ref "R22")
      (value "0")
      (footprint "R0402_0.40MM_HD")
      (description "RES 0.0 OHM 1/10W JUMP 0402 SMD")
      (fields
        (field (name "MANUFACTURER PART NUMBER") "ERJ-2GE0R00X")
        (field (name "MANUFACTURER") "Panasonic Electronic Components")
      )
      (libsource (lib "Resistors - Panasonic - AEC-Q200") (part "R_2P"))
    )
    (comp (ref "T1")
      (value "SOLDER_HOLE")
      (footprint "MACHINE_PIN_SOLDERHOLE")
      (libsource (lib "eConnector") (part "SOLDER_HOLE"))
    )
    (comp (ref "T2")
      (value "SOLDER_HOLE")
      (footprint "MACHINE_PIN_SOLDERHOLE")
      (libsource (lib "eConnector") (part "SOLDER_HOLE"))
    )
    (comp (ref "T3")
      (value "SOLDER_HOLE")
      (footprint "MACHINE_PIN_SOLDERHOLE")
      (libsource (lib "eConnector") (part "SOLDER_HOLE"))
    )
    (comp (ref "T4")
      (value "SOLDER_HOLE")
      (footprint "MACHINE_PIN_SOLDERHOLE")
      (libsource (lib "eConnector") (part "SOLDER_HOLE"))
    )
    (comp (ref "T5")
      (value "SOLDER_HOLE")
      (footprint "MACHINE_PIN_SOLDERHOLE")
      (libsource (lib "eConnector") (part "SOLDER_HOLE"))
    )
    (comp (ref "T6")
      (value "SOLDER_HOLE")
      (footprint "MACHINE_PIN_SOLDERHOLE")
      (libsource (lib "eConnector") (part "SOLDER_HOLE"))
    )
    (comp (ref "T7")
      (value "SOLDER_HOLE")
      (footprint "MACHINE_PIN_SOLDERHOLE")
      (libsource (lib "eConnector") (part "SOLDER_HOLE"))
    )
    (comp (ref "T8")
      (value "SOLDER_HOLE")
      (footprint "MACHINE_PIN_SOLDERHOLE")
      (libsource (lib "eConnector") (part "SOLDER_HOLE"))
    )
    (comp (ref "T9")
      (value "SOLDER_HOLE")
      (footprint "MACHINE_PIN_SOLDERHOLE")
      (libsource (lib "eConnector") (part "SOLDER_HOLE"))
    )
    (comp (ref "T10")
      (value "SOLDER_HOLE")
      (footprint "MACHINE_PIN_SOLDERHOLE")
      (libsource (lib "eConnector") (part "SOLDER_HOLE"))
    )
    (comp (ref "T11")
      (value "SOLDER_HOLE")
      (footprint "MACHINE_PIN_SOLDERHOLE")
      (libsource (lib "eConnector") (part "SOLDER_HOLE"))
    )
    (comp (ref "T12")
      (value "SOLDER_HOLE")
      (footprint "MACHINE_PIN_SOLDERHOLE")
      (libsource (lib "eConnector") (part "SOLDER_HOLE"))
    )
    (comp (ref "T13")
      (value "SOLDER_HOLE")
      (footprint "MACHINE_PIN_SOLDERHOLE")
      (libsource (lib "eConnector") (part "SOLDER_HOLE"))
    )
    (comp (ref "T14")
      (value "SOLDER_HOLE")
      (footprint "MACHINE_PIN_SOLDERHOLE")
      (libsource (lib "eConnector") (part "SOLDER_HOLE"))
    )
    (comp (ref "T15")
      (value "SOLDER_HOLE")
      (footprint "MACHINE_PIN_SOLDERHOLE")
      (libsource (lib "eConnector") (part "SOLDER_HOLE"))
    )
    (comp (ref "T16")
      (value "SOLDER_HOLE")
      (footprint "MACHINE_PIN_SOLDERHOLE")
      (libsource (lib "eConnector") (part "SOLDER_HOLE"))
    )
    (comp (ref "T17")
      (value "SOLDER_HOLE")
      (footprint "MACHINE_PIN_SOLDERHOLE")
      (libsource (lib "eConnector") (part "SOLDER_HOLE"))
    )
    (comp (ref "T18")
      (value "SOLDER_HOLE")
      (footprint "MACHINE_PIN_SOLDERHOLE")
      (libsource (lib "eConnector") (part "SOLDER_HOLE"))
    )
    (comp (ref "T19")
      (value "SOLDER_HOLE")
      (footprint "MACHINE_PIN_SOLDERHOLE")
      (libsource (lib "eConnector") (part "SOLDER_HOLE"))
    )
    (comp (ref "T20")
      (value "SOLDER_HOLE")
      (footprint "MACHINE_PIN_SOLDERHOLE")
      (libsource (lib "eConnector") (part "SOLDER_HOLE"))
    )
    (comp (ref "T21")
      (value "SOLDER_HOLE")
      (footprint "MACHINE_PIN_SOLDERHOLE")
      (libsource (lib "eConnector") (part "SOLDER_HOLE"))
    )
    (comp (ref "T22")
      (value "SOLDER_HOLE")
      (footprint "MACHINE_PIN_SOLDERHOLE")
      (libsource (lib "eConnector") (part "SOLDER_HOLE"))
    )
    (comp (ref "T23")
      (value "SOLDER_HOLE")
      (footprint "MACHINE_PIN_SOLDERHOLE")
      (libsource (lib "eConnector") (part "SOLDER_HOLE"))
    )
    (comp (ref "T24")
      (value "SOLDER_HOLE")
      (footprint "MACHINE_PIN_SOLDERHOLE")
      (libsource (lib "eConnector") (part "SOLDER_HOLE"))
    )
    (comp (ref "T25")
      (value "SOLDER_HOLE")
      (footprint "MACHINE_PIN_SOLDERHOLE")
      (libsource (lib "eConnector") (part "SOLDER_HOLE"))
    )
    (comp (ref "T26")
      (value "SOLDER_HOLE")
      (footprint "MACHINE_PIN_SOLDERHOLE")
      (libsource (lib "eConnector") (part "SOLDER_HOLE"))
    )
    (comp (ref "T27")
      (value "SOLDER_HOLE")
      (footprint "MACHINE_PIN_SOLDERHOLE")
      (libsource (lib "eConnector") (part "SOLDER_HOLE"))
    )
    (comp (ref "T28")
      (value "SOLDER_HOLE")
      (footprint "MACHINE_PIN_SOLDERHOLE")
      (libsource (lib "eConnector") (part "SOLDER_HOLE"))
    )
    (comp (ref "T29")
      (value "SOLDER_HOLE")
      (footprint "MACHINE_PIN_SOLDERHOLE")
      (libsource (lib "eConnector") (part "SOLDER_HOLE"))
    )
    (comp (ref "T30")
      (value "SOLDER_HOLE")
      (footprint "MACHINE_PIN_SOLDERHOLE")
      (libsource (lib "eConnector") (part "SOLDER_HOLE"))
    )
    (comp (ref "T31")
      (value "SOLDER_HOLE")
      (footprint "MACHINE_PIN_SOLDERHOLE")
      (libsource (lib "eConnector") (part "SOLDER_HOLE"))
    )
    (comp (ref "T32")
      (value "SOLDER_HOLE")
      (footprint "MACHINE_PIN_SOLDERHOLE")
      (libsource (lib "eConnector") (part "SOLDER_HOLE"))
    )
    (comp (ref "T33")
      (value "SOLDER_HOLE")
      (footprint "MACHINE_PIN_SOLDERHOLE")
      (libsource (lib "eConnector") (part "SOLDER_HOLE"))
    )
    (comp (ref "T34")
      (value "SOLDER_HOLE")
      (footprint "MACHINE_PIN_SOLDERHOLE")
      (libsource (lib "eConnector") (part "SOLDER_HOLE"))
    )
    (comp (ref "T35")
      (value "SOLDER_HOLE")
      (footprint "MACHINE_PIN_SOLDERHOLE")
      (libsource (lib "eConnector") (part "SOLDER_HOLE"))
    )
    (comp (ref "T36")
      (value "SOLDER_HOLE")
      (footprint "MACHINE_PIN_SOLDERHOLE")
      (libsource (lib "eConnector") (part "SOLDER_HOLE"))
    )
    (comp (ref "T37")
      (value "SOLDER_HOLE")
      (footprint "MACHINE_PIN_SOLDERHOLE")
      (libsource (lib "eConnector") (part "SOLDER_HOLE"))
    )
    (comp (ref "T38")
      (value "SOLDER_HOLE")
      (footprint "MACHINE_PIN_SOLDERHOLE")
      (libsource (lib "eConnector") (part "SOLDER_HOLE"))
    )
    (comp (ref "T39")
      (value "SOLDER_HOLE")
      (footprint "MACHINE_PIN_SOLDERHOLE")
      (libsource (lib "eConnector") (part "SOLDER_HOLE"))
    )
    (comp (ref "T40")
      (value "SOLDER_HOLE")
      (footprint "MACHINE_PIN_SOLDERHOLE")
      (libsource (lib "eConnector") (part "SOLDER_HOLE"))
    )
    (comp (ref "T41")
      (value "SOLDER_HOLE")
      (footprint "MACHINE_PIN_SOLDERHOLE")
      (libsource (lib "eConnector") (part "SOLDER_HOLE"))
    )
    (comp (ref "T42")
      (value "SOLDER_HOLE")
      (footprint "MACHINE_PIN_SOLDERHOLE")
      (libsource (lib "eConnector") (part "SOLDER_HOLE"))
    )
    (comp (ref "T43")
      (value "SOLDER_HOLE")
      (footprint "MACHINE_PIN_SOLDERHOLE")
      (libsource (lib "eConnector") (part "SOLDER_HOLE"))
    )
    (comp (ref "T44")
      (value "SOLDER_HOLE")
      (footprint "MACHINE_PIN_SOLDERHOLE")
      (libsource (lib "eConnector") (part "SOLDER_HOLE"))
    )
    (comp (ref "T45")
      (value "SOLDER_HOLE")
      (footprint "MACHINE_PIN_SOLDERHOLE")
      (libsource (lib "eConnector") (part "SOLDER_HOLE"))
    )
    (comp (ref "T46")
      (value "SOLDER_HOLE")
      (footprint "MACHINE_PIN_SOLDERHOLE")
      (libsource (lib "eConnector") (part "SOLDER_HOLE"))
    )
    (comp (ref "T47")
      (value "SOLDER_HOLE")
      (footprint "MACHINE_PIN_SOLDERHOLE")
      (libsource (lib "eConnector") (part "SOLDER_HOLE"))
    )
    (comp (ref "T48")
      (value "SOLDER_HOLE")
      (footprint "MACHINE_PIN_SOLDERHOLE")
      (libsource (lib "eConnector") (part "SOLDER_HOLE"))
    )
    (comp (ref "T49")
      (value "SOLDER_HOLE")
      (footprint "MACHINE_PIN_SOLDERHOLE")
      (libsource (lib "eConnector") (part "SOLDER_HOLE"))
    )
    (comp (ref "T50")
      (value "SOLDER_HOLE")
      (footprint "MACHINE_PIN_SOLDERHOLE")
      (libsource (lib "eConnector") (part "SOLDER_HOLE"))
    )
    (comp (ref "T51")
      (value "SOLDER_HOLE")
      (footprint "MACHINE_PIN_SOLDERHOLE")
      (libsource (lib "eConnector") (part "SOLDER_HOLE"))
    )
    (comp (ref "T52")
      (value "SOLDER_HOLE")
      (footprint "MACHINE_PIN_SOLDERHOLE")
      (libsource (lib "eConnector") (part "SOLDER_HOLE"))
    )
    (comp (ref "T53")
      (value "SOLDER_HOLE")
      (footprint "MACHINE_PIN_SOLDERHOLE")
      (libsource (lib "eConnector") (part "SOLDER_HOLE"))
    )
    (comp (ref "T54")
      (value "SOLDER_HOLE")
      (footprint "MACHINE_PIN_SOLDERHOLE")
      (libsource (lib "eConnector") (part "SOLDER_HOLE"))
    )
    (comp (ref "T55")
      (value "SOLDER_HOLE")
      (footprint "MACHINE_PIN_SOLDERHOLE")
      (libsource (lib "eConnector") (part "SOLDER_HOLE"))
    )
    (comp (ref "T56")
      (value "SOLDER_HOLE")
      (footprint "MACHINE_PIN_SOLDERHOLE")
      (libsource (lib "eConnector") (part "SOLDER_HOLE"))
    )
    (comp (ref "T57")
      (value "SOLDER_HOLE")
      (footprint "MACHINE_PIN_SOLDERHOLE")
      (libsource (lib "eConnector") (part "SOLDER_HOLE"))
    )
    (comp (ref "T58")
      (value "SOLDER_HOLE")
      (footprint "MACHINE_PIN_SOLDERHOLE")
      (libsource (lib "eConnector") (part "SOLDER_HOLE"))
    )
    (comp (ref "T59")
      (value "SOLDER_HOLE")
      (footprint "MACHINE_PIN_SOLDERHOLE")
      (libsource (lib "eConnector") (part "SOLDER_HOLE"))
    )
    (comp (ref "T60")
      (value "SOLDER_HOLE")
      (footprint "MACHINE_PIN_SOLDERHOLE")
      (libsource (lib "eConnector") (part "SOLDER_HOLE"))
    )
    (comp (ref "T61")
      (value "SOLDER_HOLE")
      (footprint "MACHINE_PIN_SOLDERHOLE")
      (libsource (lib "eConnector") (part "SOLDER_HOLE"))
    )
    (comp (ref "T62")
      (value "SOLDER_HOLE")
      (footprint "MACHINE_PIN_SOLDERHOLE")
      (libsource (lib "eConnector") (part "SOLDER_HOLE"))
    )
    (comp (ref "T63")
      (value "SOLDER_HOLE")
      (footprint "MACHINE_PIN_SOLDERHOLE")
      (libsource (lib "eConnector") (part "SOLDER_HOLE"))
    )
    (comp (ref "T64")
      (value "SOLDER_HOLE")
      (footprint "MACHINE_PIN_SOLDERHOLE")
      (libsource (lib "eConnector") (part "SOLDER_HOLE"))
    )
    (comp (ref "T65")
      (value "SOLDER_HOLE")
      (footprint "MACHINE_PIN_SOLDERHOLE")
      (libsource (lib "eConnector") (part "SOLDER_HOLE"))
    )
    (comp (ref "T66")
      (value "SOLDER_HOLE")
      (footprint "MACHINE_PIN_SOLDERHOLE")
      (libsource (lib "eConnector") (part "SOLDER_HOLE"))
    )
    (comp (ref "T67")
      (value "SOLDER_HOLE")
      (footprint "MACHINE_PIN_SOLDERHOLE")
      (libsource (lib "eConnector") (part "SOLDER_HOLE"))
    )
    (comp (ref "T68")
      (value "SOLDER_HOLE")
      (footprint "MACHINE_PIN_SOLDERHOLE")
      (libsource (lib "eConnector") (part "SOLDER_HOLE"))
    )
    (comp (ref "T69")
      (value "SOLDER_HOLE")
      (footprint "MACHINE_PIN_SOLDERHOLE")
      (libsource (lib "eConnector") (part "SOLDER_HOLE"))
    )
    (comp (ref "T70")
      (value "SOLDER_HOLE")
      (footprint "MACHINE_PIN_SOLDERHOLE")
      (libsource (lib "eConnector") (part "SOLDER_HOLE"))
    )
    (comp (ref "T71")
      (value "SOLDER_HOLE")
      (footprint "MACHINE_PIN_SOLDERHOLE")
      (libsource (lib "eConnector") (part "SOLDER_HOLE"))
    )
    (comp (ref "T72")
      (value "SOLDER_HOLE")
      (footprint "MACHINE_PIN_SOLDERHOLE")
      (libsource (lib "eConnector") (part "SOLDER_HOLE"))
    )
    (comp (ref "T73")
      (value "SOLDER_HOLE")
      (footprint "MACHINE_PIN_SOLDERHOLE")
      (libsource (lib "eConnector") (part "SOLDER_HOLE"))
    )
    (comp (ref "T74")
      (value "SOLDER_HOLE")
      (footprint "MACHINE_PIN_SOLDERHOLE")
      (libsource (lib "eConnector") (part "SOLDER_HOLE"))
    )
    (comp (ref "T75")
      (value "SOLDER_HOLE")
      (footprint "MACHINE_PIN_SOLDERHOLE")
      (libsource (lib "eConnector") (part "SOLDER_HOLE"))
    )
    (comp (ref "T76")
      (value "SOLDER_HOLE")
      (footprint "MACHINE_PIN_SOLDERHOLE")
      (libsource (lib "eConnector") (part "SOLDER_HOLE"))
    )
    (comp (ref "TP1")
      (value "SMT_TEST")
      (footprint "SMT_TP - 20")
      (libsource (lib "eTestPoint") (part "SMT_TEST"))
    )
    (comp (ref "U1")
      (value "MIMXRT685SFVKB")
      (footprint "VFBGA176")
      (description "SOC i.MX ARM Cortex M33 176-Pin VFBGA Tray")
      (fields (field (name "MANUFACTURER") "NXP Semiconductors"))
      (libsource (lib "eIC") (part "MIMXRT685SFVKB"))
    )
    (comp (ref "U2")
      (value "PCA9420BSAZ")
      (footprint "PCA9420")
      (description "Power Management IC for Low-Power Microcontroller Applications 24-Pin HVQFN")
      (fields (field (name "MANUFACTURER") "NXP Semiconductors"))
      (libsource (lib "eIC") (part "PCA9420BSAZ"))
    )
    (comp (ref "U3")
      (value "SN74AUC1G07DBVR")
      (footprint "SOT23-5")
      (description "IC BUFF NON-INVERT 2.7 V SOT23-5")
      (fields (field (name "MANUFACTURER") "Texas Instruments"))
      (libsource (lib "eIC") (part "SN74AUC1G07DBVR"))
    )
    (comp (ref "U4")
      (value "PRTR5V0U2X,215")
      (footprint "SOT143B")
      (description "TVS DIODE 5.5VWM SOT143B")
      (fields (field (name "MANUFACTURER") "NXP Semiconductors"))
      (libsource (lib "eDiode") (part "PRTR5V0U2X,215"))
    )
    (comp (ref "U6")
      (value "APS6408L-3OBM-BA")
      (footprint "BGA24C100P5X5_600X800X120")
      (description "3.3v Double-Data-Rate Octal SPI Xccela PSRAM")
      (fields (field (name "MANUFACTURER") "AP Memory"))
      (libsource (lib "eIC") (part "APS6408L-3OBM-BA"))
    )
    (comp (ref "X1")
      (value "32.768kHz")
      (footprint "XTAL_3215")
      (description "CRYSTAL 32.768KHZ 9PF SMD")
      (fields
        (field (name "MANUFACTURER") "NDK")
        (field (name "MANUFACTURER PART NUMBER") "NX3215SA-32.768K-STD-MUA-9")
      )
      (libsource (lib "RT_SUPER__MK76__A") (part "NX3215SA-32.768K-STD-MUA-9"))
    )
    (comp (ref "X2")
      (value "24MHz")
      (footprint "ABM3")
      (description "CRYSTAL 24.000MHZ 18PF SMD")
      (fields
        (field (name "MANUFACTURER") "Abracon Corporation")
        (field (name "MANUFACTURER PART NUMBER") "ABM3-24.000MHZ-B2-T")
      )
      (libsource (lib "wn__Crystal") (part "ABM3-24.000MHZ-B2-T"))
    )
  )
  (nets
    (net (code "1") (name "+1v8") (class "Default")
      (node (ref "C36") (pin "2") (pinfunction "2_2") (pintype "passive"))
      (node (ref "C37") (pin "2") (pinfunction "2_2") (pintype "passive"))
      (node (ref "C38") (pin "2") (pinfunction "2_2") (pintype "passive"))
      (node (ref "C39") (pin "2") (pinfunction "2_2") (pintype "passive"))
      (node (ref "C40") (pin "2") (pinfunction "2_2") (pintype "passive"))
      (node (ref "C41") (pin "2") (pinfunction "2_2") (pintype "passive"))
      (node (ref "R10") (pin "2") (pinfunction "2_2") (pintype "passive"))
      (node (ref "R21") (pin "1") (pinfunction "1_1") (pintype "passive"))
      (node (ref "U1") (pin "A13") (pinfunction "VDD1V8_1_A13") (pintype "power_in"))
      (node (ref "U1") (pin "B11") (pinfunction "VDD1V8_B11") (pintype "power_in"))
      (node (ref "U1") (pin "C16") (pinfunction "VDD1V8_C16") (pintype "power_in"))
      (node (ref "U1") (pin "C17") (pinfunction "VDD1V8_C17") (pintype "power_in"))
      (node (ref "U1") (pin "C4") (pinfunction "VDDA_BIAS_C4") (pintype "power_in"))
      (node (ref "U1") (pin "E15") (pinfunction "VDD1V8_E15") (pintype "power_in"))
      (node (ref "U1") (pin "E4") (pinfunction "VDDA_ADC1V8_E4") (pintype "power_in"))
      (node (ref "U1") (pin "F13") (pinfunction "VDD1V8_F13") (pintype "power_in"))
      (node (ref "U1") (pin "G14") (pinfunction "VDD1V8_G14") (pintype "power_in"))
      (node (ref "U1") (pin "L4") (pinfunction "VDD1V8_L4") (pintype "power_in"))
      (node (ref "U1") (pin "R15") (pinfunction "VDD1V8_R15") (pintype "power_in"))
    )
    (net (code "2") (name "+1v8_AO") (class "Default")
      (node (ref "C10") (pin "2") (pinfunction "1_2") (pintype "passive"))
      (node (ref "R2") (pin "2") (pinfunction "2_2") (pintype "passive"))
      (node (ref "R5") (pin "2") (pinfunction "2_2") (pintype "passive"))
      (node (ref "U1") (pin "C13") (pinfunction "VDD_AO1V8_C13") (pintype "power_in"))
      (node (ref "U1") (pin "D13") (pinfunction "VDD_AO1V8_D13") (pintype "power_in"))
      (node (ref "U2") (pin "12") (pinfunction "LDO1_OUT_12") (pintype "power_in"))
      (node (ref "U3") (pin "5") (pinfunction "VCC_5") (pintype "passive"))
    )
    (net (code "3") (name "+3v3") (class "Default")
      (node (ref "C12") (pin "2") (pinfunction "2_2") (pintype "passive"))
      (node (ref "C13") (pin "2") (pinfunction "2_2") (pintype "passive"))
      (node (ref "C14") (pin "2") (pinfunction "2_2") (pintype "passive"))
      (node (ref "C15") (pin "2") (pinfunction "2_2") (pintype "passive"))
      (node (ref "C16") (pin "2") (pinfunction "2_2") (pintype "passive"))
      (node (ref "C17") (pin "2") (pinfunction "2_2") (pintype "passive"))
      (node (ref "C18") (pin "2") (pinfunction "1_2") (pintype "passive"))
      (node (ref "C20") (pin "2") (pinfunction "2_2") (pintype "passive"))
      (node (ref "C21") (pin "2") (pinfunction "2_2") (pintype "passive"))
      (node (ref "C22") (pin "2") (pinfunction "2_2") (pintype "passive"))
      (node (ref "C23") (pin "2") (pinfunction "2_2") (pintype "passive"))
      (node (ref "C24") (pin "2") (pinfunction "2_2") (pintype "passive"))
      (node (ref "C25") (pin "2") (pinfunction "2_2") (pintype "passive"))
      (node (ref "C42") (pin "1") (pinfunction "1_1") (pintype "passive"))
      (node (ref "C43") (pin "1") (pinfunction "1_1") (pintype "passive"))
      (node (ref "J1") (pin "1") (pinfunction "VCC_1") (pintype "passive"))
      (node (ref "J2") (pin "1") (pinfunction "VCC_1") (pintype "passive"))
      (node (ref "R12") (pin "2") (pinfunction "2_2") (pintype "passive"))
      (node (ref "R13") (pin "2") (pinfunction "2_2") (pintype "passive"))
      (node (ref "R14") (pin "2") (pinfunction "2_2") (pintype "passive"))
      (node (ref "R22") (pin "2") (pinfunction "2_2") (pintype "passive"))
      (node (ref "R3") (pin "2") (pinfunction "2_2") (pintype "passive"))
      (node (ref "R4") (pin "2") (pinfunction "2_2") (pintype "passive"))
      (node (ref "R8") (pin "2") (pinfunction "2_2") (pintype "passive"))
      (node (ref "R9") (pin "2") (pinfunction "2_2") (pintype "passive"))
      (node (ref "T50") (pin "1") (pinfunction "1_1") (pintype "passive"))
      (node (ref "U1") (pin "E10") (pinfunction "VDDIO_1_E10") (pintype "power_in"))
      (node (ref "U1") (pin "E6") (pinfunction "VDDIO_1_E6") (pintype "power_in"))
      (node (ref "U1") (pin "E8") (pinfunction "VDDIO_1_E8") (pintype "power_in"))
      (node (ref "U1") (pin "F5") (pinfunction "VDDIO_0_F5") (pintype "power_in"))
      (node (ref "U1") (pin "H13") (pinfunction "VDDIO_1_H13") (pintype "power_in"))
      (node (ref "U1") (pin "H14") (pinfunction "VDDIO_1_H14") (pintype "power_in"))
      (node (ref "U1") (pin "H5") (pinfunction "VDDIO_0_H5") (pintype "power_in"))
      (node (ref "U1") (pin "K13") (pinfunction "VDDIO_1_K13") (pintype "power_in"))
      (node (ref "U1") (pin "K5") (pinfunction "VDDIO_0_K5") (pintype "power_in"))
      (node (ref "U1") (pin "L14") (pinfunction "VDDIO_1_L14") (pintype "power_in"))
      (node (ref "U1") (pin "M5") (pinfunction "VDDIO_0_M5") (pintype "power_in"))
      (node (ref "U1") (pin "N10") (pinfunction "VDDIO_0_N10") (pintype "power_in"))
      (node (ref "U1") (pin "N12") (pinfunction "VDDIO_2_N12") (pintype "power_in"))
      (node (ref "U1") (pin "N16") (pinfunction "USB1_VDD3V3_N16") (pintype "power_in"))
      (node (ref "U1") (pin "N6") (pinfunction "VDDIO_0_N6") (pintype "power_in"))
      (node (ref "U1") (pin "N8") (pinfunction "VDDIO_0_N8") (pintype "power_in"))
      (node (ref "U1") (pin "P11") (pinfunction "VDDIO_2_P11") (pintype "power_in"))
      (node (ref "U1") (pin "P12") (pinfunction "VDDIO_2_P12") (pintype "power_in"))
      (node (ref "U6") (pin "B4") (pinfunction "VDD_B4") (pintype "power_in"))
      (node (ref "U6") (pin "D1") (pinfunction "VDDQ_D1") (pintype "power_in"))
      (node (ref "U6") (pin "E4") (pinfunction "VDDQ_E4") (pintype "power_in"))
    )
    (net (code "4") (name "+5vUSB") (class "Default")
      (node (ref "D2") (pin "1") (pinfunction "A_1") (pintype "passive"))
      (node (ref "T55") (pin "1") (pinfunction "1_1") (pintype "passive"))
      (node (ref "U1") (pin "R16") (pinfunction "USB1_VBUS_R16") (pintype "input"))
      (node (ref "U4") (pin "4") (pinfunction "VCC_4") (pintype "passive"))
    )
    (net (code "5") (name "+VBATT") (class "Default")
      (node (ref "C4") (pin "2") (pinfunction "1_2") (pintype "passive"))
      (node (ref "R6") (pin "2") (pinfunction "2_2") (pintype "passive"))
      (node (ref "T56") (pin "1") (pinfunction "1_1") (pintype "passive"))
      (node (ref "U2") (pin "18") (pinfunction "VBAT_18") (pintype "power_in"))
    )
    (net (code "6") (name "+VBATT_BU") (class "Default")
      (node (ref "C3") (pin "2") (pinfunction "1_2") (pintype "passive"))
      (node (ref "R6") (pin "1") (pinfunction "1_1") (pintype "passive"))
      (node (ref "T53") (pin "1") (pinfunction "1_1") (pintype "passive"))
      (node (ref "U2") (pin "13") (pinfunction "VBAT_BKUP_13") (pintype "power_in"))
    )
    (net (code "7") (name "+VIN") (class "Default")
      (node (ref "D1") (pin "1") (pinfunction "A_1") (pintype "passive"))
      (node (ref "T57") (pin "1") (pinfunction "1_1") (pintype "passive"))
    )
    (net (code "8") (name "+VREF") (class "Default")
      (node (ref "C6") (pin "2") (pinfunction "2_2") (pintype "passive"))
      (node (ref "R21") (pin "2") (pinfunction "2_2") (pintype "passive"))
      (node (ref "T1") (pin "1") (pinfunction "1_1") (pintype "passive"))
      (node (ref "U1") (pin "D2") (pinfunction "VREFP_D2") (pintype "power_in"))
    )
    (net (code "9") (name "/ADC0_1") (class "Default")
      (node (ref "T74") (pin "1") (pinfunction "1_1") (pintype "passive"))
      (node (ref "U1") (pin "E3") (pinfunction "PIO0_12/FC1_SSEL2/SCT0_GPI2/SCT0_OUT2/CTIMER_INP3/SEC_PIO0_12/ADC0_1_E3") (pintype "passive"))
    )
    (net (code "10") (name "/ADC0_3") (class "Default")
      (node (ref "T75") (pin "1") (pinfunction "1_1") (pintype "passive"))
      (node (ref "U1") (pin "A2") (pinfunction "PIO0_26/FC3_SSEL2/SCT0_GPI6/SCT0_OUT6/CTIMER_INP7/SEC_PIO0_26/ADC0_3_A2") (pintype "passive"))
    )
    (net (code "11") (name "/ADC0_4") (class "Default")
      (node (ref "T73") (pin "1") (pinfunction "1_1") (pintype "passive"))
      (node (ref "U1") (pin "B5") (pinfunction "PIO1_8/FC5_SSEL2/SCT0_GPI6/CTIMER_INP12/CTIMER1_MAT2/ADC0_4_B5") (pintype "passive"))
    )
    (net (code "12") (name "/ADC0_8") (class "Default")
      (node (ref "T2") (pin "1") (pinfunction "1_1") (pintype "passive"))
      (node (ref "U1") (pin "E1") (pinfunction "PIO0_6/FC0_SSEL3/SCT0_GPI1/SCT0_OUT1/CTIMER0_MAT0/SEC_PIO0_6/ADC0_8_E1") (pintype "passive"))
    )
    (net (code "13") (name "/ADC0_12") (class "Default")
      (node (ref "T76") (pin "1") (pinfunction "1_1") (pintype "passive"))
      (node (ref "U1") (pin "B1") (pinfunction "PIO1_9/FC5_SSEL3/SCT0_GPI7/UTICK_CAP1/CTIMER1_MAT3/ADC0_12_B1") (pintype "passive"))
    )
    (net (code "14") (name "/DM_MCU") (class "Default")
      (node (ref "T43") (pin "1") (pinfunction "1_1") (pintype "passive"))
      (node (ref "U1") (pin "T17") (pinfunction "USB1_DM_T17") (pintype "bidirectional"))
      (node (ref "U4") (pin "2") (pinfunction "IO1_2") (pintype "passive"))
    )
    (net (code "15") (name "/DP_MCU") (class "Default")
      (node (ref "T45") (pin "1") (pinfunction "1_1") (pintype "passive"))
      (node (ref "U1") (pin "R17") (pinfunction "USB1_DP_R17") (pintype "bidirectional"))
      (node (ref "U4") (pin "3") (pinfunction "IO2_3") (pintype "passive"))
    )
    (net (code "16") (name "/FC0_CLK") (class "Default")
      (node (ref "T5") (pin "1") (pinfunction "1_1") (pintype "passive"))
      (node (ref "U1") (pin "G1") (pinfunction "PIO0_0/FC0_SCK/CTIMER0_MAT0/I2S_BRIDGE_CLK_IN/GPIO_INT_BMAT/SEC_PIO0_0_G1") (pintype "passive"))
    )
    (net (code "17") (name "/FC0_RXD") (class "Default")
      (node (ref "T3") (pin "1") (pinfunction "1_1") (pintype "passive"))
      (node (ref "U1") (pin "G4") (pinfunction "PIO0_2/FC0_RXD_SDA_MOSI_DATA/CTIMER0_MAT2/I2S_BRIDGE_DATA_IN/SEC_PIO0_2_G4") (pintype "passive"))
    )
    (net (code "18") (name "/FC0_SSEL0") (class "Default")
      (node (ref "T6") (pin "1") (pinfunction "1_1") (pintype "passive"))
      (node (ref "U1") (pin "H2") (pinfunction "PIO0_3/FC0_CTS_SDA_SSEL0/CTIMER0_MAT3/FC1_SSEL2/SEC_PIO0_3_H2") (pintype "passive"))
    )
    (net (code "19") (name "/FC0_SSEL1") (class "Default")
      (node (ref "T7") (pin "1") (pinfunction "1_1") (pintype "passive"))
      (node (ref "U1") (pin "J1") (pinfunction "PIO0_4/FC0_RTS_SCL_SSEL1/CTIMER_INP0/FC1_SSEL3/CMP0_OUT/SEC_PIO0_4_J1") (pintype "passive"))
    )
    (net (code "20") (name "/FC0_TXD") (class "Default")
      (node (ref "T4") (pin "1") (pinfunction "1_1") (pintype "passive"))
      (node (ref "U1") (pin "G2") (pinfunction "PIO0_1/FC0_TXD_SCL_MISO_WS/CTIMER0_MAT1/I2S_BRIDGE_WS_IN/SEC_PIO0_1_G2") (pintype "passive"))
    )
    (net (code "21") (name "/FC1_CLK") (class "Default")
      (node (ref "T8") (pin "1") (pinfunction "1_1") (pintype "passive"))
      (node (ref "U1") (pin "J2") (pinfunction "PIO0_7/FC1_SCK/SCT0_GPI4/SCT0_OUT4/CTIMER1_MAT0/I2S_BRIDGE_CLK_OUT/SEC_PIO0_7_J2") (pintype "passive"))
    )
    (net (code "22") (name "/FC1_RXD") (class "Default")
      (node (ref "T10") (pin "1") (pinfunction "1_1") (pintype "passive"))
      (node (ref "U1") (pin "L3") (pinfunction "PIO0_9/FC1_RXD_SDA_MOSI_DATA/SCT0_GPI6/SCT0_OUT6/CTIMER1_MAT2/I2S_BRIDGE_DATA_OUT/SEC_PIO0_9_L3") (pintype "passive"))
    )
    (net (code "23") (name "/FC1_SSEL0") (class "Default")
      (node (ref "T9") (pin "1") (pinfunction "1_1") (pintype "passive"))
      (node (ref "U1") (pin "J3") (pinfunction "PIO0_10/FC1_CTS_SDA_SSEL0/SCT0_GPI7/SCT0_OUT7/CTIMER1_MAT3/FC0_SSEL2/SEC_PIO0_10_J3") (pintype "passive"))
    )
    (net (code "24") (name "/FC1_SSEL1") (class "Default")
      (node (ref "T12") (pin "1") (pinfunction "1_1") (pintype "passive"))
      (node (ref "U1") (pin "L1") (pinfunction "PIO0_11/FC1_RTS_SCL_SSEL1/SCT0_GPI0/SCT0_OUT8/CTIMER_INP2/FC0_SSEL3/SEC_PIO0_11_L1") (pintype "passive"))
    )
    (net (code "25") (name "/FC1_TXD") (class "Default")
      (node (ref "T11") (pin "1") (pinfunction "1_1") (pintype "passive"))
      (node (ref "U1") (pin "K4") (pinfunction "PIO0_8/FC1_TXD_SCL_MISO_WS/SCT0_GPI5/SCT0_OUT5/CTIMER1_MAT1/I2S_BRIDGE_WS_OUT/SEC_PIO0_8_K4") (pintype "passive"))
    )
    (net (code "26") (name "/FC2_CLK") (class "Default")
      (node (ref "T62") (pin "1") (pinfunction "1_1") (pintype "passive"))
      (node (ref "U1") (pin "A3") (pinfunction "PIO0_14/FC2_SCK/SCT0_GPI0/SCT0_OUT0/CTIMER2_MAT0/I2S_BRIDGE_CLK_IN/SEC_PIO0_14_A3") (pintype "passive"))
    )
    (net (code "27") (name "/FC2_SDA") (class "Default")
      (node (ref "T59") (pin "1") (pinfunction "1_1") (pintype "passive"))
      (node (ref "U1") (pin "D6") (pinfunction "PIO0_16/FC2_RXD_SDA_MOSI_DATA/SCT0_GPI2/SCT0_OUT2/CTIMER2_MAT2/I2S_BRIDGE_DATA_IN/SEC_PIO0_16_D6") (pintype "passive"))
    )
    (net (code "28") (name "/FC2_SSEL0") (class "Default")
      (node (ref "T58") (pin "1") (pinfunction "1_1") (pintype "passive"))
      (node (ref "U1") (pin "D7") (pinfunction "PIO0_17/FC2_CTS_SDA_SSEL0/SCT0_GPI3/SCT0_OUT3/CTIMER2_MAT3/FC5_SSEL2/SEC_PIO0_17_D7") (pintype "passive"))
    )
    (net (code "29") (name "/FC2_SSEL1") (class "Default")
      (node (ref "T60") (pin "1") (pinfunction "1_1") (pintype "passive"))
      (node (ref "U1") (pin "B7") (pinfunction "PIO0_18/FC2_RTS_SCL_SSEL1/SCT0_GPI6/SCT0_OUT6/CTIMER_INP4/FC5_SSEL3/SEC_PIO0_18_B7") (pintype "passive"))
    )
    (net (code "30") (name "/FC2_WS") (class "Default")
      (node (ref "T61") (pin "1") (pinfunction "1_1") (pintype "passive"))
      (node (ref "U1") (pin "A5") (pinfunction "PIO0_15/FC2_TXD_SCL_MISO_WS/SCT0_GPI1/SCT0_OUT1/CTIMER2_MAT1/I2S_BRIDGE_WS_IN/SEC_PIO0_15_A5") (pintype "passive"))
    )
    (net (code "31") (name "/FC3_CLK") (class "Default")
      (node (ref "T72") (pin "1") (pinfunction "1_1") (pintype "passive"))
      (node (ref "U1") (pin "C7") (pinfunction "PIO0_21/FC3_SCK/CTIMER3_MAT0/TRACECLK/SEC_PIO0_21_C7") (pintype "passive"))
    )
    (net (code "32") (name "/FC3_SDA") (class "Default")
      (node (ref "T70") (pin "1") (pinfunction "1_1") (pintype "passive"))
      (node (ref "U1") (pin "C9") (pinfunction "PIO0_23/FC3_RXD_SDA_MOSI_DATA/CTIMER3_MAT2/TRACEDATA(1)/SEC_PIO0_23_C9") (pintype "passive"))
    )
    (net (code "33") (name "/FC3_SSEL0") (class "Default")
      (node (ref "T68") (pin "1") (pinfunction "1_1") (pintype "passive"))
      (node (ref "U1") (pin "B9") (pinfunction "PIO0_24/FC3_CTS_SDA_SSEL0/CTIMER3_MAT3/FC2_SSEL2/TRACEDATA(2)/CLKOUT/SEC_PIO0_24_B9") (pintype "passive"))
    )
    (net (code "34") (name "/FC3_SSEL1") (class "Default")
      (node (ref "T69") (pin "1") (pinfunction "1_1") (pintype "passive"))
      (node (ref "U1") (pin "A9") (pinfunction "PIO0_25/FC3_RTS_SCL_SSEL1/FREQME_GPIO_CLK/CTIMER_INP6/FC2_SSEL3/TRACEDATA(3)/CLKIN/SEC_PIO0_25_A9") (pintype "passive"))
    )
    (net (code "35") (name "/FC3_WS") (class "Default")
      (node (ref "T71") (pin "1") (pinfunction "1_1") (pintype "passive"))
      (node (ref "U1") (pin "D8") (pinfunction "PIO0_22/FC3_TXD_SCL_MISO_WS/CTIMER3_MAT1/TRACEDATA(0)/SEC_PIO0_22_D8") (pintype "passive"))
    )
    (net (code "36") (name "/FC4_CLK") (class "Default")
      (node (ref "T64") (pin "1") (pinfunction "1_1") (pintype "passive"))
      (node (ref "U1") (pin "D11") (pinfunction "PIO0_28/FC4_SCK/CTIMER4_MAT0/I2S_BRIDGE_CLK_OUT/SEC_PIO0_28_D11") (pintype "passive"))
    )
    (net (code "37") (name "/FC4_SDA") (class "Default")
      (node (ref "T65") (pin "1") (pinfunction "1_1") (pintype "passive"))
      (node (ref "U1") (pin "C11") (pinfunction "PIO0_30/FC4_RXD_SDA_MOSI_DATA/CTIMER4_MAT2/I2S_BRIDGE_DATA_OUT/SEC_PIO0_30_C11") (pintype "passive"))
    )
    (net (code "38") (name "/FC4_SSEL0") (class "Default")
      (node (ref "T66") (pin "1") (pinfunction "1_1") (pintype "passive"))
      (node (ref "U1") (pin "A11") (pinfunction "PIO0_31/FC4_CTS_SDA_SSEL0/SCT0_GPI0/SCT0_OUT6/CTIMER4_MAT3/FC3_SSEL2/SEC_PIO0_31_A11") (pintype "passive"))
    )
    (net (code "39") (name "/FC4_SSEL1") (class "Default")
      (node (ref "T63") (pin "1") (pinfunction "1_1") (pintype "passive"))
      (node (ref "U1") (pin "E17") (pinfunction "PIO1_0/FC4_RTS_SCL_SSEL1/SCT0_GPI1/SCT0_OUT7/CTIMER_INP8/FC3_SSEL3_E17") (pintype "passive"))
    )
    (net (code "40") (name "/FC4_WS") (class "Default")
      (node (ref "T67") (pin "1") (pinfunction "1_1") (pintype "passive"))
      (node (ref "U1") (pin "B10") (pinfunction "PIO0_29/FC4_TXD_SCL_MISO_WS/CTIMER4_MAT1/I2S_BRIDGE_WS_OUT/SEC_PIO0_29_B10") (pintype "passive"))
    )
    (net (code "41") (name "/FC5_RXD") (class "Default")
      (node (ref "T42") (pin "1") (pinfunction "1_1") (pintype "passive"))
      (node (ref "U1") (pin "J16") (pinfunction "PIO1_5/FC5_RXD_SDA_MOSI_DATA_J16") (pintype "passive"))
    )
    (net (code "42") (name "/FC5_SCK") (class "Default")
      (node (ref "T47") (pin "1") (pinfunction "1_1") (pintype "passive"))
      (node (ref "U1") (pin "G16") (pinfunction "PIO1_3/FC5_SCK_G16") (pintype "passive"))
    )
    (net (code "43") (name "/FC5_SSEL0") (class "Default")
      (node (ref "T44") (pin "1") (pinfunction "1_1") (pintype "passive"))
      (node (ref "U1") (pin "J17") (pinfunction "PIO1_6/FC5_CTS_SDA_SSEL0/SCT0_GPI4/SCT0_OUT4/FC4_SSEL2_J17") (pintype "passive"))
    )
    (net (code "44") (name "/FC5_TXD") (class "Default")
      (node (ref "T46") (pin "1") (pinfunction "1_1") (pintype "passive"))
      (node (ref "U1") (pin "G17") (pinfunction "PIO1_4/FC5_TXD_SCL_MISO_WS_G17") (pintype "passive"))
    )
    (net (code "45") (name "/FLEXSPI0A_D0") (class "Default")
      (node (ref "U1") (pin "T5") (pinfunction "PIO1_20/FLEXSPI0A_DATA0/SCT0_GPI1/CTIMER4_MAT1_T5") (pintype "passive"))
      (node (ref "U6") (pin "D3") (pinfunction "ADQ0_D3") (pintype "bidirectional"))
    )
    (net (code "46") (name "/FLEXSPI0A_D1") (class "Default")
      (node (ref "U1") (pin "U5") (pinfunction "PIO1_21/FLEXSPI0A_DATA1/SCT0_OUT1/CTIMER4_MAT2_U5") (pintype "passive"))
      (node (ref "U6") (pin "D2") (pinfunction "ADQ1_D2") (pintype "bidirectional"))
    )
    (net (code "47") (name "/FLEXSPI0A_D2") (class "Default")
      (node (ref "U1") (pin "P6") (pinfunction "PIO1_22/FLEXSPI0A_DATA2/SCT0_GPI2/CTIMER4_MAT3_P6") (pintype "passive"))
      (node (ref "U6") (pin "C4") (pinfunction "ADQ2_C4") (pintype "bidirectional"))
    )
    (net (code "48") (name "/FLEXSPI0A_D3") (class "Default")
      (node (ref "U1") (pin "P7") (pinfunction "PIO1_23/FLEXSPI0A_DATA3/SCT0_OUT2/CTIMER_INP8_P7") (pintype "passive"))
      (node (ref "U6") (pin "D4") (pinfunction "ADQ3_D4") (pintype "bidirectional"))
    )
    (net (code "49") (name "/FLEXSPI0A_D4") (class "Default")
      (node (ref "U1") (pin "T7") (pinfunction "PIO1_24/FLEXSPI0A_DATA4/SCT0_GPI3_T7") (pintype "passive"))
      (node (ref "U6") (pin "D5") (pinfunction "ADQ4_D5") (pintype "bidirectional"))
    )
    (net (code "50") (name "/FLEXSPI0A_D5") (class "Default")
      (node (ref "U1") (pin "U7") (pinfunction "PIO1_25/FLEXSPI0A_DATA5/SCT0_OUT3_U7") (pintype "passive"))
      (node (ref "U6") (pin "E3") (pinfunction "ADQ5_E3") (pintype "bidirectional"))
    )
    (net (code "51") (name "/FLEXSPI0A_D6") (class "Default")
      (node (ref "U1") (pin "R7") (pinfunction "PIO1_26/FLEXSPI0A_DATA6/SCT0_GPI4_R7") (pintype "passive"))
      (node (ref "U6") (pin "E2") (pinfunction "ADQ6_E2") (pintype "bidirectional"))
    )
    (net (code "52") (name "/FLEXSPI0A_D7") (class "Default")
      (node (ref "U1") (pin "T8") (pinfunction "PIO1_27/FLEXSPI0A_DATA7/SCT0_OUT4_T8") (pintype "passive"))
      (node (ref "U6") (pin "E1") (pinfunction "ADQ7_E1") (pintype "bidirectional"))
    )
    (net (code "53") (name "/FLEXSPI0A_DQS") (class "Default")
      (node (ref "U1") (pin "U9") (pinfunction "PIO1_28/FLEXSPI0A_DQS/SCT0_GPI5_U9") (pintype "passive"))
      (node (ref "U6") (pin "C3") (pinfunction "DQS/DM_C3") (pintype "bidirectional"))
    )
    (net (code "54") (name "/FLEXSPI0A_SCK") (class "Default")
      (node (ref "U1") (pin "T9") (pinfunction "PIO1_18/FLEXSPI0A_SCLK/SCT0_GPI0/CTIMER3_MAT3_T9") (pintype "passive"))
      (node (ref "U6") (pin "B2") (pinfunction "CLK_B2") (pintype "input"))
    )
    (net (code "55") (name "/FLEXSPI0A_SS0_N") (class "Default")
      (node (ref "R9") (pin "1") (pinfunction "1_1") (pintype "passive"))
      (node (ref "U1") (pin "T4") (pinfunction "PIO1_19/FLEXSPI0A_SS0_N/SCT0_OUT0/CTIMER4_MAT0_T4") (pintype "passive"))
      (node (ref "U6") (pin "A3") (pinfunction "~{CE}_A3") (pintype "input"))
    )
    (net (code "56") (name "/FLEXSPI0B_CLK") (class "Default")
      (node (ref "T20") (pin "1") (pinfunction "1_1") (pintype "passive"))
      (node (ref "U1") (pin "U3") (pinfunction "PIO1_29/FLEXSPI0A_SS1_N/SCT0_OUT5/UTICK_CAP2/CTIMER_INP13/FLEXSPI0B_SCLK_U3") (pintype "passive"))
    )
    (net (code "57") (name "/HS_SPI_MISO") (class "Default")
      (node (ref "T14") (pin "1") (pinfunction "1_1") (pintype "passive"))
      (node (ref "U1") (pin "M2") (pinfunction "PIO1_12/HS_SPI_MISO/CTIMER2_MAT1/FLEXSPI0B_DATA1_M2") (pintype "passive"))
    )
    (net (code "58") (name "/HS_SPI_MOSI") (class "Default")
      (node (ref "T15") (pin "1") (pinfunction "1_1") (pintype "passive"))
      (node (ref "U1") (pin "N1") (pinfunction "PIO1_13/HS_SPI_MOSI/CTIMER2_MAT2/FLEXSPI0B_DATA2_N1") (pintype "passive"))
    )
    (net (code "59") (name "/HS_SPI_SCK") (class "Default")
      (node (ref "T13") (pin "1") (pinfunction "1_1") (pintype "passive"))
      (node (ref "U1") (pin "L2") (pinfunction "PIO1_11/HS_SPI_SCK/CTIMER2_MAT0/FLEXSPI0B_DATA0_L2") (pintype "passive"))
    )
    (net (code "60") (name "/HS_SPI_SSEL0") (class "Default")
      (node (ref "T16") (pin "1") (pinfunction "1_1") (pintype "passive"))
      (node (ref "U1") (pin "N2") (pinfunction "PIO1_14/HS_SPI_SSEL0/CTIMER2_MAT3/FLEXSPI0B_DATA3_N2") (pintype "passive"))
    )
    (net (code "61") (name "/I3C0_PUR") (class "Default")
      (node (ref "R16") (pin "1") (pinfunction "1_1") (pintype "passive"))
      (node (ref "U1") (pin "B6") (pinfunction "PIO2_31/I3C0_PUR/SCT0_OUT7/UTICK_CAP3/CTIMER_INP15/SWO/CMP0_B_B6") (pintype "passive"))
    )
    (net (code "62") (name "/I3C0_SCL") (class "Default")
      (node (ref "T41") (pin "1") (pinfunction "1_1") (pintype "passive"))
      (node (ref "U1") (pin "N17") (pinfunction "PIO2_29/I3C0_SCL/SCT0_OUT0/CLKOUT_N17") (pintype "passive"))
    )
    (net (code "63") (name "/I3C0_SDA") (class "Default")
      (node (ref "R16") (pin "2") (pinfunction "2_2") (pintype "passive"))
      (node (ref "T40") (pin "1") (pinfunction "1_1") (pintype "passive"))
      (node (ref "U1") (pin "P16") (pinfunction "PIO2_30/I3C0_SDA/SCT0_OUT3/CLKIN/CMP0_OUT_P16") (pintype "passive"))
    )
    (net (code "64") (name "/ISP0") (class "Default")
      (node (ref "R12") (pin "1") (pinfunction "1_1") (pintype "passive"))
      (node (ref "R15") (pin "2") (pinfunction "2_2") (pintype "passive"))
      (node (ref "T17") (pin "1") (pinfunction "1_1") (pintype "passive"))
      (node (ref "U1") (pin "N3") (pinfunction "PIO1_15/HS_SPI_SSEL1/CTIMER3_MAT0/ISP0_N3") (pintype "passive"))
    )
    (net (code "65") (name "/ISP1") (class "Default")
      (node (ref "R13") (pin "1") (pinfunction "1_1") (pintype "passive"))
      (node (ref "R17") (pin "2") (pinfunction "2_2") (pintype "passive"))
      (node (ref "T18") (pin "1") (pinfunction "1_1") (pintype "passive"))
      (node (ref "U1") (pin "M4") (pinfunction "PIO1_16/HS_SPI_SSEL2/SCT0_OUT8/CTIMER3_MAT1/ISP1_M4") (pintype "passive"))
    )
    (net (code "66") (name "/ISP2") (class "Default")
      (node (ref "R14") (pin "1") (pinfunction "1_1") (pintype "passive"))
      (node (ref "R18") (pin "2") (pinfunction "2_2") (pintype "passive"))
      (node (ref "T19") (pin "1") (pinfunction "1_1") (pintype "passive"))
      (node (ref "U1") (pin "N4") (pinfunction "PIO1_17/HS_SPI_SSEL3/SCT0_OUT9/CTIMER3_MAT2/ISP2_N4") (pintype "passive"))
    )
    (net (code "67") (name "/MCLK") (class "Default")
      (node (ref "T48") (pin "1") (pinfunction "1_1") (pintype "passive"))
      (node (ref "U1") (pin "K16") (pinfunction "PIO1_10/MCLK/FREQME_GPIO_CLK/CTIMER_INP10/CLKOUT_K16") (pintype "passive"))
    )
    (net (code "68") (name "/PDM_CLK01") (class "Default")
      (node (ref "T22") (pin "1") (pinfunction "1_1") (pintype "passive"))
      (node (ref "U1") (pin "R1") (pinfunction "PIO2_16/PDM_CLK01_R1") (pintype "passive"))
    )
    (net (code "69") (name "/PDM_CLK23") (class "Default")
      (node (ref "T24") (pin "1") (pinfunction "1_1") (pintype "passive"))
      (node (ref "U1") (pin "U1") (pinfunction "PIO2_17/PDM_CLK23/FLEXSPI0B_DATA4_U1") (pintype "passive"))
    )
    (net (code "70") (name "/PDM_CLK45") (class "Default")
      (node (ref "T26") (pin "1") (pinfunction "1_1") (pintype "passive"))
      (node (ref "U1") (pin "R2") (pinfunction "PIO2_18/PDM_CLK45/FLEXSPI0B_DATA5_R2") (pintype "passive"))
    )
    (net (code "71") (name "/PDM_CLK67") (class "Default")
      (node (ref "T28") (pin "1") (pinfunction "1_1") (pintype "passive"))
      (node (ref "U1") (pin "T2") (pinfunction "PIO2_19/PDM_CLK67/FLEXSPI0B_SS0_N_T2") (pintype "passive"))
    )
    (net (code "72") (name "/PDM_DATA01") (class "Default")
      (node (ref "T21") (pin "1") (pinfunction "1_1") (pintype "passive"))
      (node (ref "U1") (pin "U2") (pinfunction "PIO2_20/PDM_DATA01_U2") (pintype "passive"))
    )
    (net (code "73") (name "/PDM_DATA23") (class "Default")
      (node (ref "T23") (pin "1") (pinfunction "1_1") (pintype "passive"))
      (node (ref "U1") (pin "R3") (pinfunction "PIO2_21/PDM_DATA23/CTIMER_INP14/FLEXSPI0B_SS1_N_R3") (pintype "passive"))
    )
    (net (code "74") (name "/PDM_DATA45") (class "Default")
      (node (ref "T25") (pin "1") (pinfunction "1_1") (pintype "passive"))
      (node (ref "U1") (pin "P3") (pinfunction "PIO2_22/PDM_DATA45/FLEXSPI0B_DATA6_P3") (pintype "passive"))
    )
    (net (code "75") (name "/PDM_DATA67") (class "Default")
      (node (ref "T27") (pin "1") (pinfunction "1_1") (pintype "passive"))
      (node (ref "U1") (pin "P5") (pinfunction "PIO2_23/PDM_DATA67/FLEXSPI0B_DATA7_P5") (pintype "passive"))
    )
    (net (code "76") (name "/PIO0_19") (class "Default")
      (node (ref "R19") (pin "2") (pinfunction "2_2") (pintype "passive"))
      (node (ref "U1") (pin "A1") (pinfunction "PIO0_19/FC2_SSEL2/SCT0_GPI4/SCT0_OUT4/CTIMER_INP5/UTICK_CAP0/SEC_PIO0_19/ADC0_2_A1") (pintype "passive"))
    )
    (net (code "77") (name "/PIO2_4") (class "Default")
      (node (ref "T37") (pin "1") (pinfunction "1_1") (pintype "passive"))
      (node (ref "U1") (pin "T13") (pinfunction "PIO2_4/SD0_WR_PRT/SCT0_OUT2/SD0_DS_T13") (pintype "passive"))
    )
    (net (code "78") (name "/PIO2_5") (class "Default")
      (node (ref "T38") (pin "1") (pinfunction "1_1") (pintype "passive"))
      (node (ref "U1") (pin "U13") (pinfunction "PIO2_5/SD0_D4/SCT0_OUT3_U13") (pintype "passive"))
    )
    (net (code "79") (name "/PIO2_6") (class "Default")
      (node (ref "T39") (pin "1") (pinfunction "1_1") (pintype "passive"))
      (node (ref "U1") (pin "U15") (pinfunction "PIO2_6/SD0_D5/SCT0_GPI4/CTIMER1_MAT0_U15") (pintype "passive"))
    )
    (net (code "80") (name "/PMIC_INTB") (class "Default")
      (node (ref "R2") (pin "1") (pinfunction "1_1") (pintype "passive"))
      (node (ref "U1") (pin "A15") (pinfunction "~{PMIC_IRQ_N}_A15") (pintype "input"))
      (node (ref "U2") (pin "10") (pinfunction "INTB_10") (pintype "output"))
    )
    (net (code "81") (name "/PMIC_MODE0") (class "Default")
      (node (ref "U1") (pin "C15") (pinfunction "PMIC_MODE0_C15") (pintype "output"))
      (node (ref "U2") (pin "7") (pinfunction "MODESEL0_7") (pintype "input"))
    )
    (net (code "82") (name "/PMIC_MODE1") (class "Default")
      (node (ref "U1") (pin "B16") (pinfunction "PMIC_MODE1_B16") (pintype "output"))
      (node (ref "U2") (pin "8") (pinfunction "MODESEL1_8") (pintype "input"))
    )
    (net (code "83") (name "/PMIC_ON") (class "Default")
      (node (ref "T52") (pin "1") (pinfunction "1_1") (pintype "passive"))
      (node (ref "U2") (pin "4") (pinfunction "ON_4") (pintype "input"))
    )
    (net (code "84") (name "/PMIC_RESETN") (class "Default")
      (node (ref "R5") (pin "1") (pinfunction "1_1") (pintype "passive"))
      (node (ref "U1") (pin "B15") (pinfunction "~{RESETN}_B15") (pintype "input"))
      (node (ref "U2") (pin "11") (pinfunction "SYSRSTN_11") (pintype "output"))
      (node (ref "U3") (pin "4") (pinfunction "Y_4") (pintype "passive"))
    )
    (net (code "85") (name "/PMIC_SCL") (class "Default")
      (node (ref "R3") (pin "1") (pinfunction "1_1") (pintype "passive"))
      (node (ref "U1") (pin "E16") (pinfunction "PMIC_I2C_SCL_E16") (pintype "output"))
      (node (ref "U2") (pin "5") (pinfunction "SCL_5") (pintype "input"))
    )
    (net (code "86") (name "/PMIC_SDA") (class "Default")
      (node (ref "R4") (pin "1") (pinfunction "1_1") (pintype "passive"))
      (node (ref "U1") (pin "F16") (pinfunction "PMIC_I2C_SDA_F16") (pintype "bidirectional"))
      (node (ref "U2") (pin "6") (pinfunction "SDA_6") (pintype "bidirectional"))
    )
    (net (code "87") (name "/RED_LED") (class "Default")
      (node (ref "R20") (pin "2") (pinfunction "2_2") (pintype "passive"))
      (node (ref "U1") (pin "B3") (pinfunction "PIO0_27/FC3_SSEL3/SCT0_GPI7/SCT0_OUT7/CTIMER0_MAT3/SEC_PIO0_27/ADC0_11_B3") (pintype "passive"))
    )
    (net (code "88") (name "/RST_3V3") (class "Default")
      (node (ref "J1") (pin "3") (pinfunction "RST_3") (pintype "passive"))
      (node (ref "J2") (pin "10") (pinfunction "~{RST}_10") (pintype "passive"))
      (node (ref "R11") (pin "1") (pinfunction "1_1") (pintype "passive"))
      (node (ref "R8") (pin "1") (pinfunction "1_1") (pintype "passive"))
      (node (ref "T49") (pin "1") (pinfunction "1_1") (pintype "passive"))
      (node (ref "U3") (pin "2") (pinfunction "A_2") (pintype "passive"))
    )
    (net (code "89") (name "/SD_CLK") (class "Default")
      (node (ref "T34") (pin "1") (pinfunction "1_1") (pintype "passive"))
      (node (ref "U1") (pin "P10") (pinfunction "PIO1_30/SD0_CLK/SCT0_GPI0_P10") (pintype "passive"))
    )
    (net (code "90") (name "/SD_CMD") (class "Default")
      (node (ref "T29") (pin "1") (pinfunction "1_1") (pintype "passive"))
      (node (ref "U1") (pin "R9") (pinfunction "PIO1_31/SD0_CMD/SCT0_GPI1_R9") (pintype "passive"))
    )
    (net (code "91") (name "/SD_D0") (class "Default")
      (node (ref "T30") (pin "1") (pinfunction "1_1") (pintype "passive"))
      (node (ref "U1") (pin "R11") (pinfunction "PIO2_0/SD0_D0/SCT0_GPI2_R11") (pintype "passive"))
    )
    (net (code "92") (name "/SD_D1") (class "Default")
      (node (ref "T31") (pin "1") (pinfunction "1_1") (pintype "passive"))
      (node (ref "U1") (pin "T11") (pinfunction "PIO2_1/SD0_D1/SCT0_GPI3_T11") (pintype "passive"))
    )
    (net (code "93") (name "/SD_D2") (class "Default")
      (node (ref "T32") (pin "1") (pinfunction "1_1") (pintype "passive"))
      (node (ref "U1") (pin "U11") (pinfunction "PIO2_2/SD0_D2/SCT0_OUT0_U11") (pintype "passive"))
    )
    (net (code "94") (name "/SD_D3") (class "Default")
      (node (ref "T33") (pin "1") (pinfunction "1_1") (pintype "passive"))
      (node (ref "U1") (pin "T12") (pinfunction "PIO2_3/SD0_D3/SCT0_OUT1_T12") (pintype "passive"))
    )
    (net (code "95") (name "/SD_DETECT_N") (class "Default")
      (node (ref "T36") (pin "1") (pinfunction "1_1") (pintype "passive"))
      (node (ref "U1") (pin "R13") (pinfunction "PIO2_9/SD0_CARD_DET_N/SCT0_OUT5/CTIMER1_MAT3_R13") (pintype "passive"))
    )
    (net (code "96") (name "/SD_RESET_N") (class "Default")
      (node (ref "T35") (pin "1") (pinfunction "1_1") (pintype "passive"))
      (node (ref "U1") (pin "T15") (pinfunction "PIO2_10/SD0_RESET_N/SCT0_GPI6/CTIMER2_MAT0_T15") (pintype "passive"))
    )
    (net (code "97") (name "/SWCLK") (class "Default")
      (node (ref "J1") (pin "4") (pinfunction "SWDCLK_4") (pintype "passive"))
      (node (ref "J2") (pin "4") (pinfunction "SWDCLK/TCK_4") (pintype "passive"))
      (node (ref "U1") (pin "L17") (pinfunction "PIO2_25/SWCLK_L17") (pintype "passive"))
    )
    (net (code "98") (name "/SWIO") (class "Default")
      (node (ref "J1") (pin "2") (pinfunction "SWDIO_2") (pintype "passive"))
      (node (ref "J2") (pin "2") (pinfunction "SWDIO/TMS_2") (pintype "passive"))
      (node (ref "U1") (pin "L15") (pinfunction "PIO2_26/SWDIO_L15") (pintype "passive"))
    )
    (net (code "99") (name "/SWO") (class "Default")
      (node (ref "J1") (pin "6") (pinfunction "SWO_6") (pintype "passive"))
      (node (ref "J2") (pin "6") (pinfunction "SWO/TDO_6") (pintype "passive"))
      (node (ref "U1") (pin "L16") (pinfunction "PIO2_24/SWO/GPIO_INT_BMAT_L16") (pintype "passive"))
    )
    (net (code "100") (name "/TEMP_SENSE") (class "Default")
      (node (ref "T51") (pin "1") (pinfunction "1_1") (pintype "passive"))
      (node (ref "U2") (pin "14") (pinfunction "TS_14") (pintype "input"))
    )
    (net (code "101") (name "GND") (class "Default")
      (node (ref "C1") (pin "1") (pinfunction "1_1") (pintype "passive"))
      (node (ref "C10") (pin "1") (pinfunction "1_1") (pintype "passive"))
      (node (ref "C11") (pin "1") (pinfunction "1_1") (pintype "passive"))
      (node (ref "C12") (pin "1") (pinfunction "1_1") (pintype "passive"))
      (node (ref "C13") (pin "1") (pinfunction "1_1") (pintype "passive"))
      (node (ref "C14") (pin "1") (pinfunction "1_1") (pintype "passive"))
      (node (ref "C15") (pin "1") (pinfunction "1_1") (pintype "passive"))
      (node (ref "C16") (pin "1") (pinfunction "1_1") (pintype "passive"))
      (node (ref "C17") (pin "1") (pinfunction "1_1") (pintype "passive"))
      (node (ref "C18") (pin "1") (pinfunction "1_1") (pintype "passive"))
      (node (ref "C19") (pin "1") (pinfunction "1_1") (pintype "passive"))
      (node (ref "C2") (pin "2") (pinfunction "1_2") (pintype "passive"))
      (node (ref "C20") (pin "1") (pinfunction "1_1") (pintype "passive"))
      (node (ref "C21") (pin "1") (pinfunction "1_1") (pintype "passive"))
      (node (ref "C22") (pin "1") (pinfunction "1_1") (pintype "passive"))
      (node (ref "C23") (pin "1") (pinfunction "1_1") (pintype "passive"))
      (node (ref "C24") (pin "1") (pinfunction "1_1") (pintype "passive"))
      (node (ref "C25") (pin "1") (pinfunction "1_1") (pintype "passive"))
      (node (ref "C26") (pin "1") (pinfunction "1_1") (pintype "passive"))
      (node (ref "C27") (pin "1") (pinfunction "1_1") (pintype "passive"))
      (node (ref "C28") (pin "1") (pinfunction "1_1") (pintype "passive"))
      (node (ref "C29") (pin "1") (pinfunction "1_1") (pintype "passive"))
      (node (ref "C3") (pin "1") (pinfunction "1_1") (pintype "passive"))
      (node (ref "C30") (pin "1") (pinfunction "1_1") (pintype "passive"))
      (node (ref "C31") (pin "1") (pinfunction "1_1") (pintype "passive"))
      (node (ref "C32") (pin "1") (pinfunction "1_1") (pintype "passive"))
      (node (ref "C33") (pin "1") (pinfunction "1_1") (pintype "passive"))
      (node (ref "C34") (pin "1") (pinfunction "1_1") (pintype "passive"))
      (node (ref "C35") (pin "1") (pinfunction "1_1") (pintype "passive"))
      (node (ref "C36") (pin "1") (pinfunction "1_1") (pintype "passive"))
      (node (ref "C37") (pin "1") (pinfunction "1_1") (pintype "passive"))
      (node (ref "C38") (pin "1") (pinfunction "1_1") (pintype "passive"))
      (node (ref "C39") (pin "1") (pinfunction "1_1") (pintype "passive"))
      (node (ref "C4") (pin "1") (pinfunction "1_1") (pintype "passive"))
      (node (ref "C40") (pin "1") (pinfunction "1_1") (pintype "passive"))
      (node (ref "C41") (pin "1") (pinfunction "1_1") (pintype "passive"))
      (node (ref "C42") (pin "2") (pinfunction "1_2") (pintype "passive"))
      (node (ref "C43") (pin "2") (pinfunction "1_2") (pintype "passive"))
      (node (ref "C44") (pin "2") (pinfunction "1_2") (pintype "passive"))
      (node (ref "C45") (pin "2") (pinfunction "1_2") (pintype "passive"))
      (node (ref "C5") (pin "2") (pinfunction "1_2") (pintype "passive"))
      (node (ref "C6") (pin "1") (pinfunction "1_1") (pintype "passive"))
      (node (ref "C7") (pin "1") (pinfunction "1_1") (pintype "passive"))
      (node (ref "C8") (pin "2") (pinfunction "1_2") (pintype "passive"))
      (node (ref "C9") (pin "1") (pinfunction "1_1") (pintype "passive"))
      (node (ref "D3") (pin "C") (pinfunction "C_C") (pintype "passive"))
      (node (ref "D4") (pin "C") (pinfunction "C_C") (pintype "passive"))
      (node (ref "J1") (pin "5") (pinfunction "GND_5") (pintype "passive"))
      (node (ref "J2") (pin "3") (pinfunction "GND_3") (pintype "passive"))
      (node (ref "J2") (pin "5") (pinfunction "GND_5") (pintype "passive"))
      (node (ref "J2") (pin "9") (pinfunction "GND_DETECT_9") (pintype "passive"))
      (node (ref "R1") (pin "1") (pinfunction "1_1") (pintype "passive"))
      (node (ref "R15") (pin "1") (pinfunction "1_1") (pintype "passive"))
      (node (ref "R17") (pin "1") (pinfunction "1_1") (pintype "passive"))
      (node (ref "R18") (pin "1") (pinfunction "1_1") (pintype "passive"))
      (node (ref "T54") (pin "1") (pinfunction "1_1") (pintype "passive"))
      (node (ref "U1") (pin "C2") (pinfunction "VREFN_C2") (pintype "power_in"))
      (node (ref "U1") (pin "C3") (pinfunction "VSSA_C3") (pintype "power_in"))
      (node (ref "U1") (pin "D12") (pinfunction "VSSA_D12") (pintype "power_in"))
      (node (ref "U1") (pin "D15") (pinfunction "VSS_D15") (pintype "power_in"))
      (node (ref "U1") (pin "D5") (pinfunction "VSS_D5") (pintype "power_in"))
      (node (ref "U1") (pin "E12") (pinfunction "VSS_E12") (pintype "power_in"))
      (node (ref "U1") (pin "E14") (pinfunction "VSS_E14") (pintype "power_in"))
      (node (ref "U1") (pin "F11") (pinfunction "VSS_F11") (pintype "power_in"))
      (node (ref "U1") (pin "F7") (pinfunction "VSS_F7") (pintype "power_in"))
      (node (ref "U1") (pin "G12") (pinfunction "VSS_G12") (pintype "power_in"))
      (node (ref "U1") (pin "G6") (pinfunction "VSS_G6") (pintype "power_in"))
      (node (ref "U1") (pin "H10") (pinfunction "VSS_H10") (pintype "power_in"))
      (node (ref "U1") (pin "H8") (pinfunction "VSS_H8") (pintype "power_in"))
      (node (ref "U1") (pin "H9") (pinfunction "VSS_H9") (pintype "power_in"))
      (node (ref "U1") (pin "J10") (pinfunction "VSS_J10") (pintype "power_in"))
      (node (ref "U1") (pin "J8") (pinfunction "VSS_J8") (pintype "power_in"))
      (node (ref "U1") (pin "K10") (pinfunction "VSS_K10") (pintype "power_in"))
      (node (ref "U1") (pin "K8") (pinfunction "VSS_K8") (pintype "power_in"))
      (node (ref "U1") (pin "K9") (pinfunction "VSS_K9") (pintype "power_in"))
      (node (ref "U1") (pin "L12") (pinfunction "VSS_L12") (pintype "power_in"))
      (node (ref "U1") (pin "L6") (pinfunction "VSS_L6") (pintype "power_in"))
      (node (ref "U1") (pin "M11") (pinfunction "VSS_M11") (pintype "power_in"))
      (node (ref "U1") (pin "M13") (pinfunction "VSS_M13") (pintype "power_in"))
      (node (ref "U1") (pin "M7") (pinfunction "VSS_M7") (pintype "power_in"))
      (node (ref "U1") (pin "N14") (pinfunction "VSS_N14") (pintype "power_in"))
      (node (ref "U1") (pin "P13") (pinfunction "VSS_P13") (pintype "power_in"))
      (node (ref "U2") (pin "21") (pinfunction "AGND2_21") (pintype "power_in"))
      (node (ref "U2") (pin "23") (pinfunction "PGND1_23") (pintype "power_in"))
      (node (ref "U2") (pin "24") (pinfunction "PGND2_24") (pintype "power_in"))
      (node (ref "U2") (pin "25") (pinfunction "EXP_25") (pintype "power_in"))
      (node (ref "U2") (pin "9") (pinfunction "AGND1_9") (pintype "power_in"))
      (node (ref "U3") (pin "3") (pinfunction "GND_3") (pintype "passive"))
      (node (ref "U4") (pin "1") (pinfunction "GND_1") (pintype "passive"))
      (node (ref "U6") (pin "B3") (pinfunction "VSS_B3") (pintype "power_in"))
      (node (ref "U6") (pin "C1") (pinfunction "VSSQ_C1") (pintype "power_in"))
      (node (ref "U6") (pin "E5") (pinfunction "VSSQ_E5") (pintype "power_in"))
    )
    (net (code "102") (name "Net-(D1-K)") (class "Default")
      (node (ref "C1") (pin "2") (pinfunction "1_2") (pintype "passive"))
      (node (ref "D1") (pin "2") (pinfunction "K_2") (pintype "passive"))
      (node (ref "D2") (pin "2") (pinfunction "K_2") (pintype "passive"))
      (node (ref "U2") (pin "16") (pinfunction "VIN_16") (pintype "power_in"))
    )
    (net (code "103") (name "Net-(D3-PadA)") (class "Default")
      (node (ref "D3") (pin "A") (pinfunction "A_A") (pintype "passive"))
      (node (ref "R19") (pin "1") (pinfunction "1_1") (pintype "passive"))
    )
    (net (code "104") (name "Net-(D4-PadA)") (class "Default")
      (node (ref "D4") (pin "A") (pinfunction "A_A") (pintype "passive"))
      (node (ref "R20") (pin "1") (pinfunction "1_1") (pintype "passive"))
    )
    (net (code "105") (name "Net-(U1C-LDO_ENABLE)") (class "Default")
      (node (ref "R1") (pin "2") (pinfunction "2_2") (pintype "passive"))
      (node (ref "U1") (pin "A16") (pinfunction "LDO_ENABLE_A16") (pintype "input"))
    )
    (net (code "106") (name "Net-(U1H-RTCXIN)") (class "Default")
      (node (ref "C44") (pin "1") (pinfunction "1_1") (pintype "passive"))
      (node (ref "U1") (pin "B17") (pinfunction "RTCXIN_B17") (pintype "input"))
      (node (ref "X1") (pin "2") (pinfunction "OSC2_2") (pintype "passive"))
    )
    (net (code "107") (name "Net-(U1H-RTCXOUT)") (class "Default")
      (node (ref "C45") (pin "1") (pinfunction "1_1") (pintype "passive"))
      (node (ref "U1") (pin "A17") (pinfunction "RTCXOUT_A17") (pintype "output"))
      (node (ref "X1") (pin "1") (pinfunction "OSC1_1") (pintype "passive"))
    )
    (net (code "108") (name "Net-(U1H-XTALIN)") (class "Default")
      (node (ref "C11") (pin "2") (pinfunction "1_2") (pintype "passive"))
      (node (ref "U1") (pin "B14") (pinfunction "XTALIN_B14") (pintype "input"))
      (node (ref "X2") (pin "2") (pinfunction "OSC2_2") (pintype "passive"))
    )
    (net (code "109") (name "Net-(U1H-XTALOUT)") (class "Default")
      (node (ref "C19") (pin "2") (pinfunction "1_2") (pintype "passive"))
      (node (ref "U1") (pin "B13") (pinfunction "XTALOUT_B13") (pintype "output"))
      (node (ref "X2") (pin "1") (pinfunction "OSC1_1") (pintype "passive"))
    )
    (net (code "110") (name "Net-(U2-ASYS)") (class "Default")
      (node (ref "C2") (pin "1") (pinfunction "1_1") (pintype "passive"))
      (node (ref "C5") (pin "1") (pinfunction "1_1") (pintype "passive"))
      (node (ref "C8") (pin "1") (pinfunction "1_1") (pintype "passive"))
      (node (ref "U2") (pin "17") (pinfunction "ASYS_17") (pintype "power_in"))
      (node (ref "U2") (pin "2") (pinfunction "PSYS2_2") (pintype "power_in"))
      (node (ref "U2") (pin "20") (pinfunction "PSYS1_20") (pintype "power_in"))
    )
    (net (code "111") (name "Net-(U2-LDO2_OUT)") (class "Default")
      (node (ref "R22") (pin "1") (pinfunction "1_1") (pintype "passive"))
      (node (ref "U2") (pin "15") (pinfunction "LDO2_OUT_15") (pintype "power_in"))
    )
    (net (code "112") (name "Net-(U2-LX1)") (class "Default")
      (node (ref "L2") (pin "1") (pinfunction "1_1") (pintype "passive"))
      (node (ref "U2") (pin "22") (pinfunction "LX1_22") (pintype "power_in"))
    )
    (net (code "113") (name "Net-(U2-LX2)") (class "Default")
      (node (ref "L3") (pin "1") (pinfunction "1_1") (pintype "passive"))
      (node (ref "U2") (pin "1") (pinfunction "LX2_1") (pintype "power_in"))
    )
    (net (code "114") (name "Net-(U2-SW1_OUT)") (class "Default")
      (node (ref "C7") (pin "2") (pinfunction "1_2") (pintype "passive"))
      (node (ref "L2") (pin "2") (pinfunction "2_2") (pintype "passive"))
      (node (ref "R7") (pin "1") (pinfunction "1_1") (pintype "passive"))
      (node (ref "U2") (pin "19") (pinfunction "SW1_OUT_19") (pintype "input"))
    )
    (net (code "115") (name "Net-(U2-SW2_OUT)") (class "Default")
      (node (ref "C9") (pin "2") (pinfunction "1_2") (pintype "passive"))
      (node (ref "L3") (pin "2") (pinfunction "2_2") (pintype "passive"))
      (node (ref "R10") (pin "1") (pinfunction "1_1") (pintype "passive"))
      (node (ref "U2") (pin "3") (pinfunction "SW2_OUT_3") (pintype "input"))
    )
    (net (code "116") (name "Net-(U6-RFU)") (class "Default")
      (node (ref "TP1") (pin "1") (pinfunction "1_1") (pintype "passive"))
      (node (ref "U6") (pin "C2") (pinfunction "RFU_C2") (pintype "passive"))
    )
    (net (code "117") (name "Net-(U6-~{RESET})") (class "Default")
      (node (ref "R11") (pin "2") (pinfunction "2_2") (pintype "passive"))
      (node (ref "U6") (pin "A4") (pinfunction "~{RESET}_A4") (pintype "input"))
    )
    (net (code "118") (name "VDD_CORE") (class "Default")
      (node (ref "C26") (pin "2") (pinfunction "2_2") (pintype "passive"))
      (node (ref "C27") (pin "2") (pinfunction "2_2") (pintype "passive"))
      (node (ref "C28") (pin "2") (pinfunction "2_2") (pintype "passive"))
      (node (ref "C29") (pin "2") (pinfunction "2_2") (pintype "passive"))
      (node (ref "C30") (pin "2") (pinfunction "2_2") (pintype "passive"))
      (node (ref "C31") (pin "2") (pinfunction "2_2") (pintype "passive"))
      (node (ref "C32") (pin "2") (pinfunction "2_2") (pintype "passive"))
      (node (ref "C33") (pin "2") (pinfunction "2_2") (pintype "passive"))
      (node (ref "C34") (pin "2") (pinfunction "2_2") (pintype "passive"))
      (node (ref "C35") (pin "2") (pinfunction "2_2") (pintype "passive"))
      (node (ref "R7") (pin "2") (pinfunction "2_2") (pintype "passive"))
      (node (ref "U1") (pin "C5") (pinfunction "VDDCORE_C5") (pintype "power_in"))
      (node (ref "U1") (pin "D9") (pinfunction "VDDCORE_D9") (pintype "power_in"))
      (node (ref "U1") (pin "F14") (pinfunction "VDDCORE_F14") (pintype "power_in"))
      (node (ref "U1") (pin "J14") (pinfunction "VDDCORE_J14") (pintype "power_in"))
      (node (ref "U1") (pin "J4") (pinfunction "VDDCORE_J4") (pintype "power_in"))
      (node (ref "U1") (pin "P9") (pinfunction "VDDCORE_P9") (pintype "power_in"))
      (node (ref "U1") (pin "R14") (pinfunction "VDDCORE_R14") (pintype "power_in"))
      (node (ref "U1") (pin "R5") (pinfunction "VDDCORE_R5") (pintype "power_in"))
    )
    (net (code "119") (name "unconnected-(J2-KEY-Pad7)") (class "Default")
      (node (ref "J2") (pin "7") (pinfunction "KEY_7") (pintype "passive+no_connect"))
    )
    (net (code "120") (name "unconnected-(J2-TDI-Pad8)") (class "Default")
      (node (ref "J2") (pin "8") (pinfunction "TDI_8") (pintype "passive+no_connect"))
    )
    (net (code "121") (name "unconnected-(U1D-PIO0_5{slash}FC0_SSEL2{slash}SCT0_GPI0{slash}SCT0_OUT0{slash}CTIMER_INP1{slash}SEC_PIO0_5{slash}ADC0_0-PadF4)") (class "Default")
      (node (ref "U1") (pin "F4") (pinfunction "PIO0_5/FC0_SSEL2/SCT0_GPI0/SCT0_OUT0/CTIMER_INP1/SEC_PIO0_5/ADC0_0_F4") (pintype "passive+no_connect"))
    )
    (net (code "122") (name "unconnected-(U1D-PIO0_13{slash}FC1_SSEL3{slash}SCT0_GPI3{slash}SCT0_OUT3{slash}CTIMER0_MAT1{slash}SEC_PIO0_13{slash}ADC0_9-PadG3)") (class "Default")
      (node (ref "U1") (pin "G3") (pinfunction "PIO0_13/FC1_SSEL3/SCT0_GPI3/SCT0_OUT3/CTIMER0_MAT1/SEC_PIO0_13/ADC0_9_G3") (pintype "passive+no_connect"))
    )
    (net (code "123") (name "unconnected-(U1D-PIO2_12{slash}SCT0_OUT6{slash}CTIMER2_MAT2-PadT3)") (class "Default")
      (node (ref "U1") (pin "T3") (pinfunction "PIO2_12/SCT0_OUT6/CTIMER2_MAT2_T3") (pintype "passive+no_connect"))
    )
    (net (code "124") (name "unconnected-(U1D-PIO2_13{slash}SCT0_OUT7{slash}CTIMER2_MAT3{slash}CMP0_OUT-PadT1)") (class "Default")
      (node (ref "U1") (pin "T1") (pinfunction "PIO2_13/SCT0_OUT7/CTIMER2_MAT3/CMP0_OUT_T1") (pintype "passive+no_connect"))
    )
    (net (code "125") (name "unconnected-(U1D-PIO2_14{slash}SCT0_OUT8{slash}CTIMER_INP1{slash}CMP0_A-PadC1)") (class "Default")
      (node (ref "U1") (pin "C1") (pinfunction "PIO2_14/SCT0_OUT8/CTIMER_INP1/CMP0_A_C1") (pintype "passive+no_connect"))
    )
    (net (code "126") (name "unconnected-(U1D-PIO2_15{slash}SCT0_OUT9{slash}CLKIN{slash}CMP0_D-PadE2)") (class "Default")
      (node (ref "U1") (pin "E2") (pinfunction "PIO2_15/SCT0_OUT9/CLKIN/CMP0_D_E2") (pintype "passive+no_connect"))
    )
    (net (code "127") (name "unconnected-(U1E-PIO0_20{slash}FC2_SSEL3{slash}SCT0_GPI5{slash}SCT0_OUT5{slash}CTIMER0_MAT2{slash}CTIMER_INP11{slash}SEC_PIO0_20{slash}ADC0_10-PadB2)") (class "Default")
      (node (ref "U1") (pin "B2") (pinfunction "PIO0_20/FC2_SSEL3/SCT0_GPI5/SCT0_OUT5/CTIMER0_MAT2/CTIMER_INP11/SEC_PIO0_20/ADC0_10_B2") (pintype "passive+no_connect"))
    )
    (net (code "128") (name "unconnected-(U1E-PIO1_1{slash}FC4_SSEL2{slash}SCT0_GPI2{slash}SCT0_OUT8{slash}CTIMER1_MAT0-PadG15)") (class "Default")
      (node (ref "U1") (pin "G15") (pinfunction "PIO1_1/FC4_SSEL2/SCT0_GPI2/SCT0_OUT8/CTIMER1_MAT0_G15") (pintype "passive+no_connect"))
    )
    (net (code "129") (name "unconnected-(U1E-PIO1_2{slash}FC4_SSEL3{slash}SCT0_GPI3{slash}SCT0_OUT9{slash}CTIMER1_MAT1{slash}CMP0_C-PadA7)") (class "Default")
      (node (ref "U1") (pin "A7") (pinfunction "PIO1_2/FC4_SSEL3/SCT0_GPI3/SCT0_OUT9/CTIMER1_MAT1/CMP0_C_A7") (pintype "passive+no_connect"))
    )
    (net (code "130") (name "unconnected-(U1E-PIO1_7{slash}FC5_RTS_SCL_SSEL1{slash}SCT0_GPI5{slash}SCT0_OUT5{slash}CTIMER_INP9{slash}FC4_SSEL3-PadJ15)") (class "Default")
      (node (ref "U1") (pin "J15") (pinfunction "PIO1_7/FC5_RTS_SCL_SSEL1/SCT0_GPI5/SCT0_OUT5/CTIMER_INP9/FC4_SSEL3_J15") (pintype "passive+no_connect"))
    )
    (net (code "131") (name "unconnected-(U1E-PIO2_27{slash}USB1_OVERCURRENTN-PadM14)") (class "Default")
      (node (ref "U1") (pin "M14") (pinfunction "PIO2_27/USB1_OVERCURRENTN_M14") (pintype "passive+no_connect"))
    )
    (net (code "132") (name "unconnected-(U1E-PIO2_28{slash}USB1_PORTPWRN-PadN15)") (class "Default")
      (node (ref "U1") (pin "N15") (pinfunction "PIO2_28/USB1_PORTPWRN_N15") (pintype "passive+no_connect"))
    )
    (net (code "133") (name "unconnected-(U1F-PIO2_7{slash}SD0_D6{slash}SCT0_GPI5{slash}CTIMER1_MAT1-PadU16)") (class "Default")
      (node (ref "U1") (pin "U16") (pinfunction "PIO2_7/SD0_D6/SCT0_GPI5/CTIMER1_MAT1_U16") (pintype "passive+no_connect"))
    )
    (net (code "134") (name "unconnected-(U1F-PIO2_8{slash}SD0_D7{slash}SCT0_OUT4{slash}CTIMER1_MAT2-PadU17)") (class "Default")
      (node (ref "U1") (pin "U17") (pinfunction "PIO2_8/SD0_D7/SCT0_OUT4/CTIMER1_MAT2_U17") (pintype "passive+no_connect"))
    )
    (net (code "135") (name "unconnected-(U1F-PIO2_11{slash}SD0_VOLT{slash}SCT0_GPI7{slash}CTIMER2_MAT1-PadT16)") (class "Default")
      (node (ref "U1") (pin "T16") (pinfunction "PIO2_11/SD0_VOLT/SCT0_GPI7/CTIMER2_MAT1_T16") (pintype "passive+no_connect"))
    )
    (net (code "136") (name "unconnected-(U6-NC-PadA2)") (class "Default")
      (node (ref "U6") (pin "A2") (pinfunction "NC_A2") (pintype "passive+no_connect"))
    )
    (net (code "137") (name "unconnected-(U6-NC-PadA5)") (class "Default")
      (node (ref "U6") (pin "A5") (pinfunction "NC_A5") (pintype "passive+no_connect"))
    )
    (net (code "138") (name "unconnected-(U6-NC-PadB1)") (class "Default")
      (node (ref "U6") (pin "B1") (pinfunction "NC_B1") (pintype "passive+no_connect"))
    )
    (net (code "139") (name "unconnected-(U6-NC-PadB5)") (class "Default")
      (node (ref "U6") (pin "B5") (pinfunction "NC_B5") (pintype "passive+no_connect"))
    )
    (net (code "140") (name "unconnected-(U6-NC-PadC5)") (class "Default")
      (node (ref "U6") (pin "C5") (pinfunction "NC_C5") (pintype "passive+no_connect"))
    )
  )
)
